# PX4uNode_V0_1_2.net
KiCad netlist of a schematic drawn in EAGLE
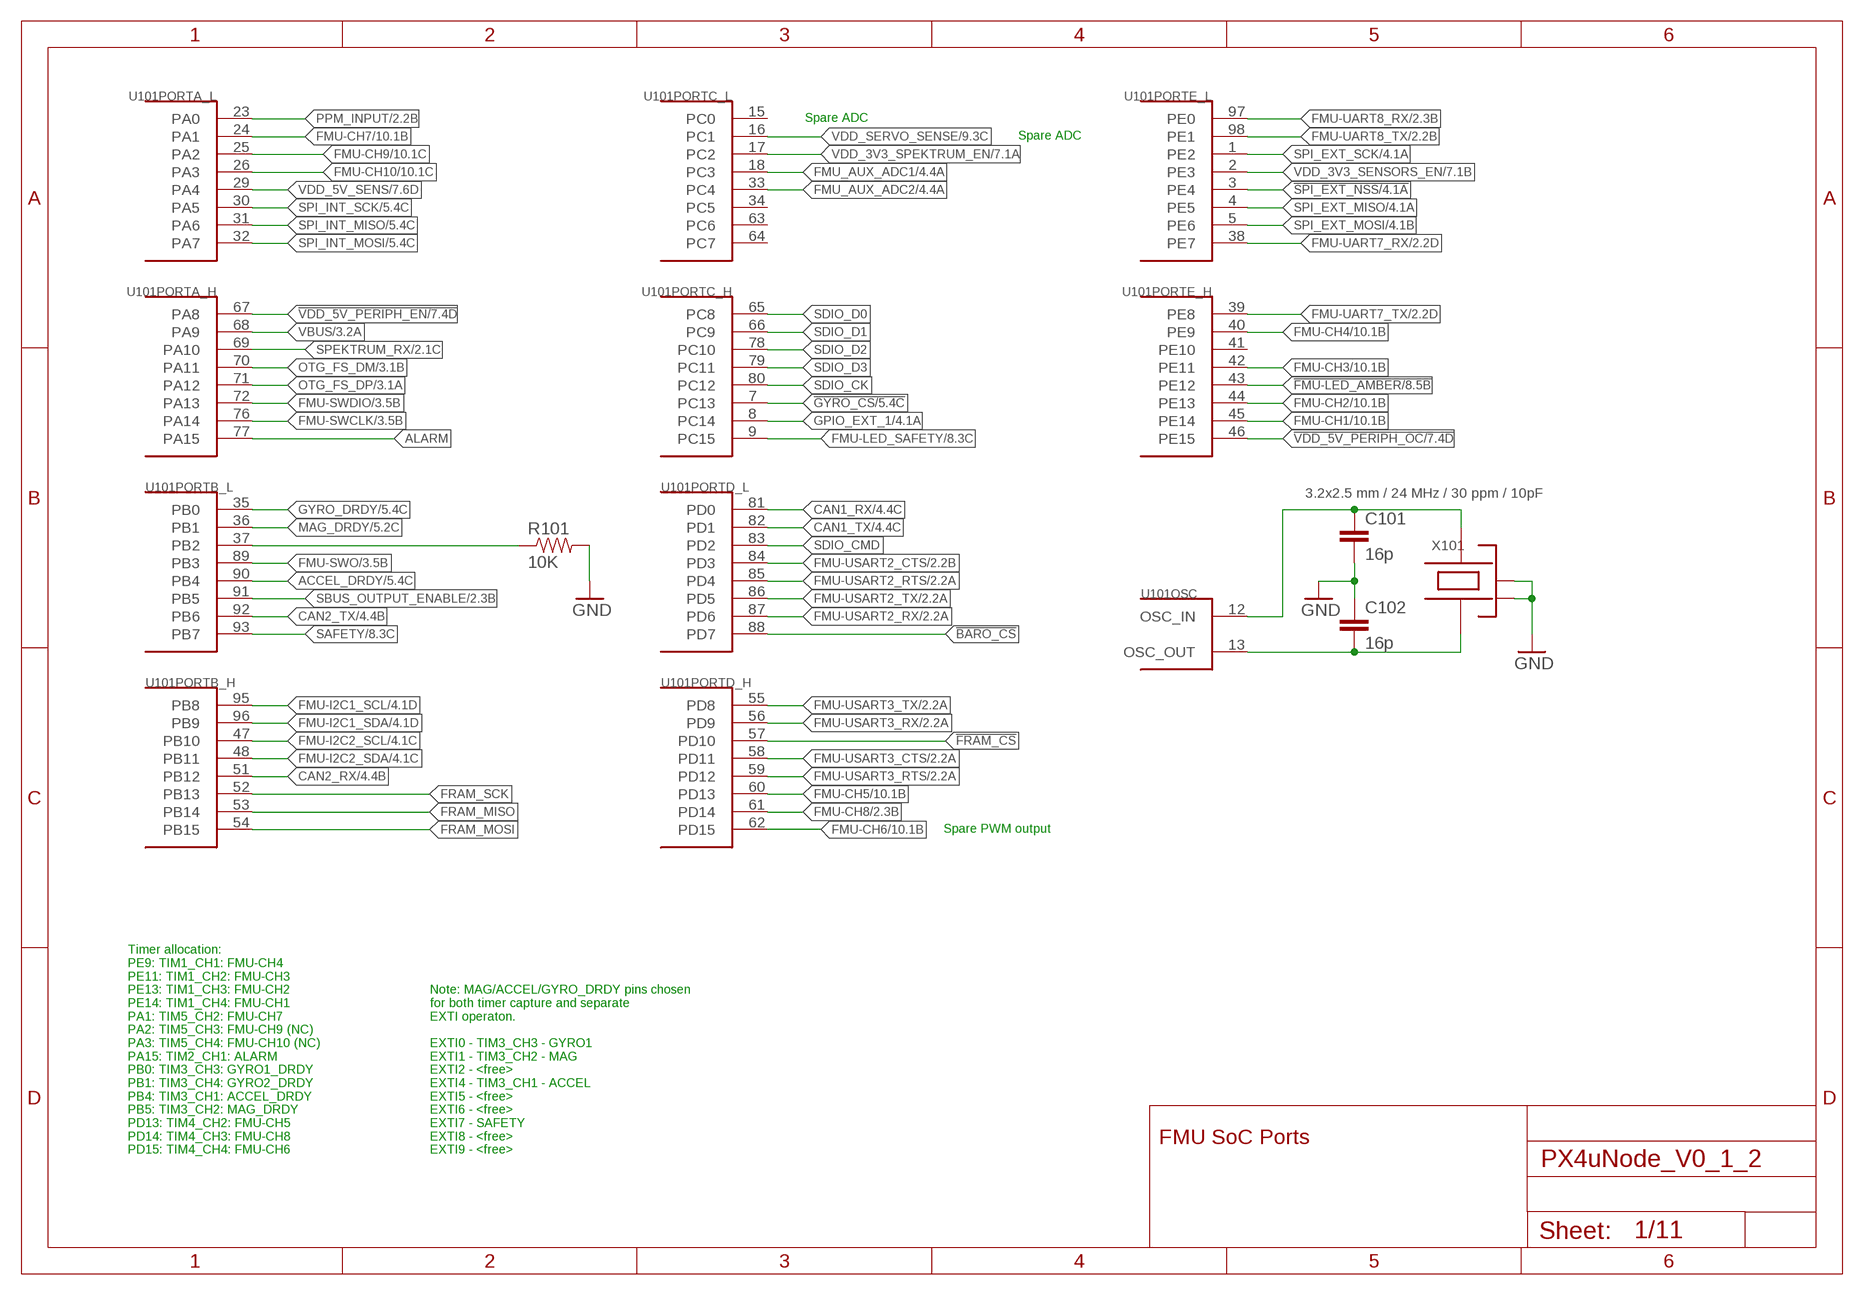
[diagram p0: schematic, sheet 1]
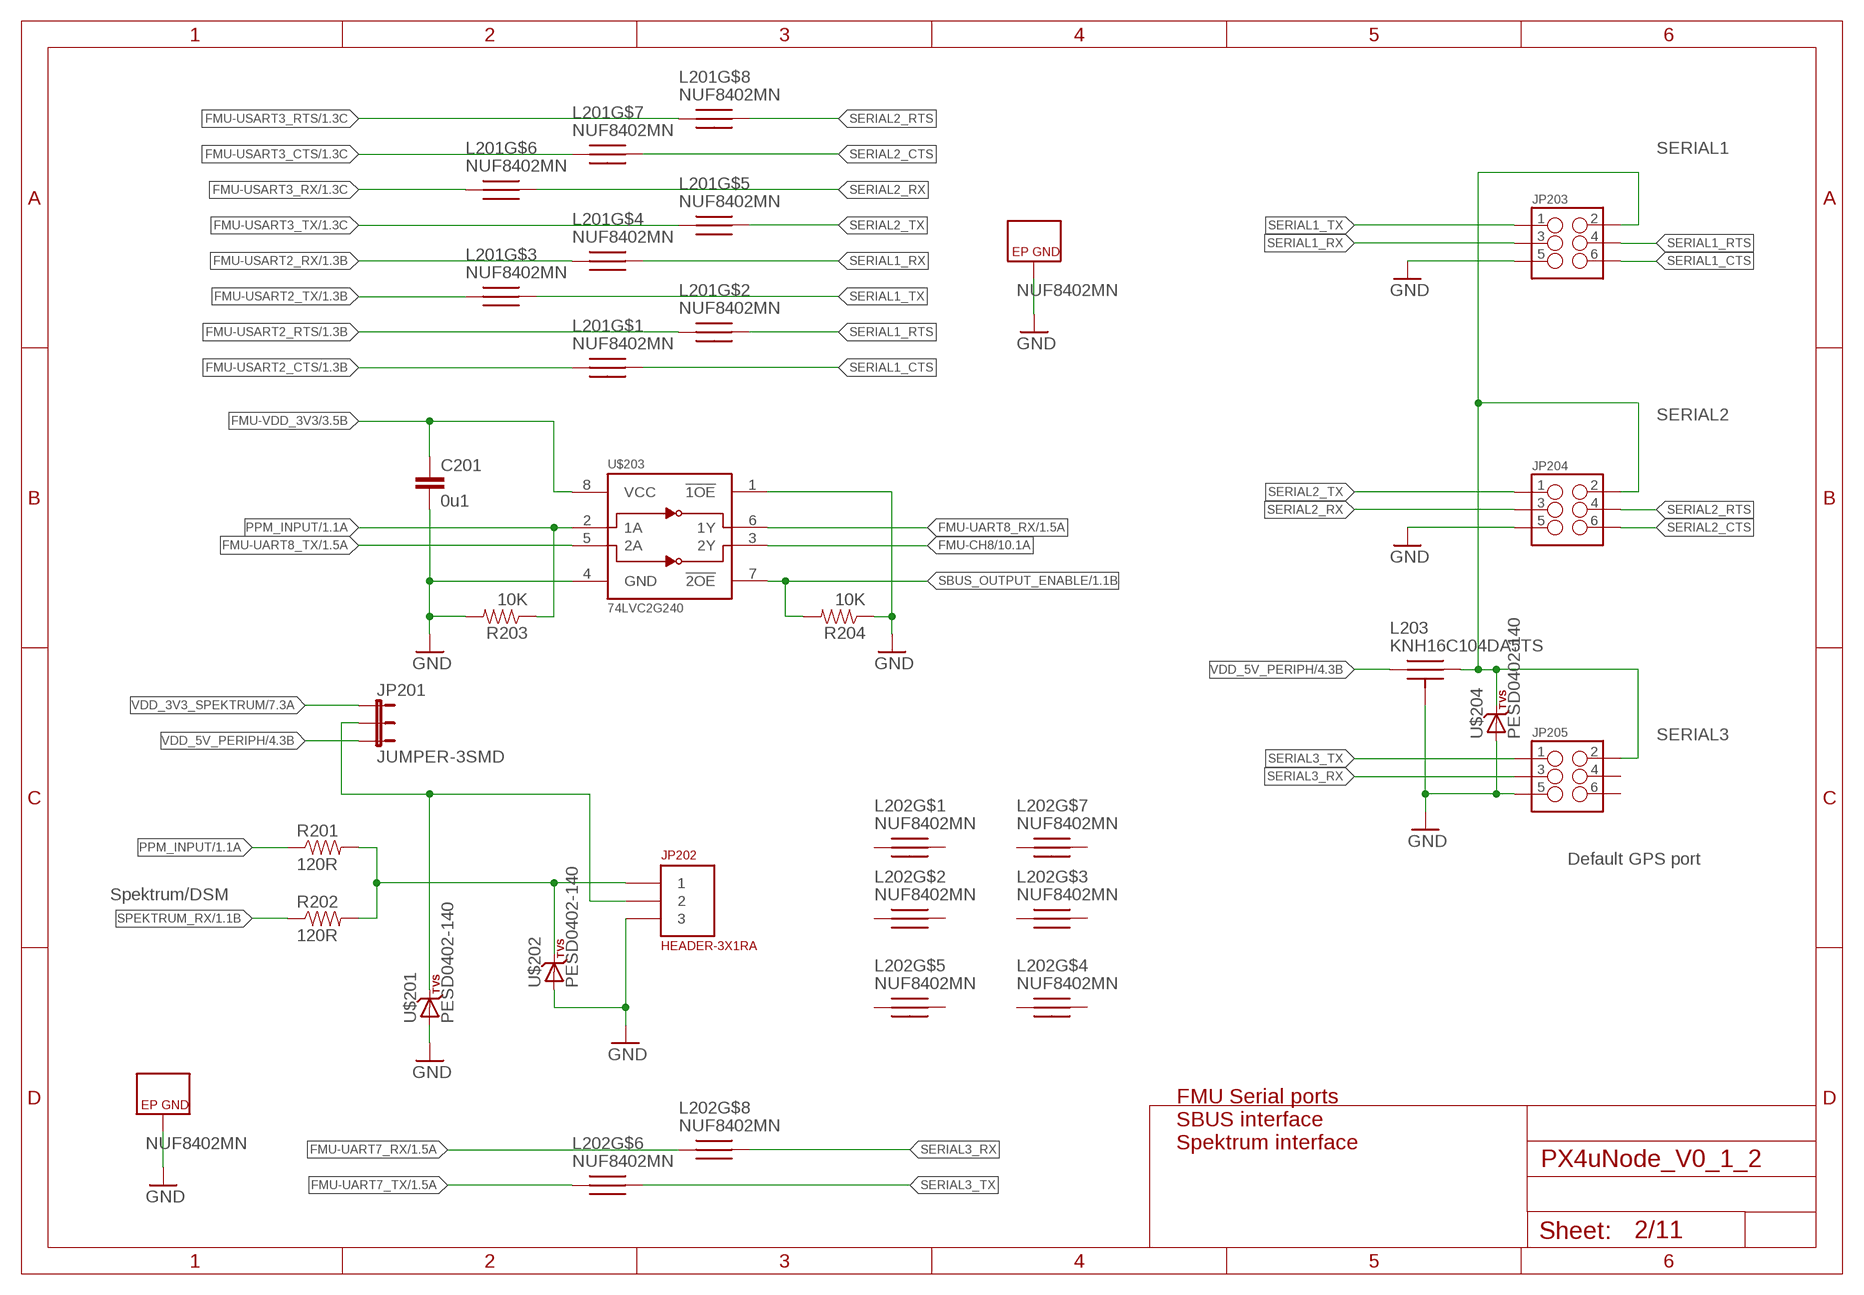
[diagram p1: schematic, sheet 2]
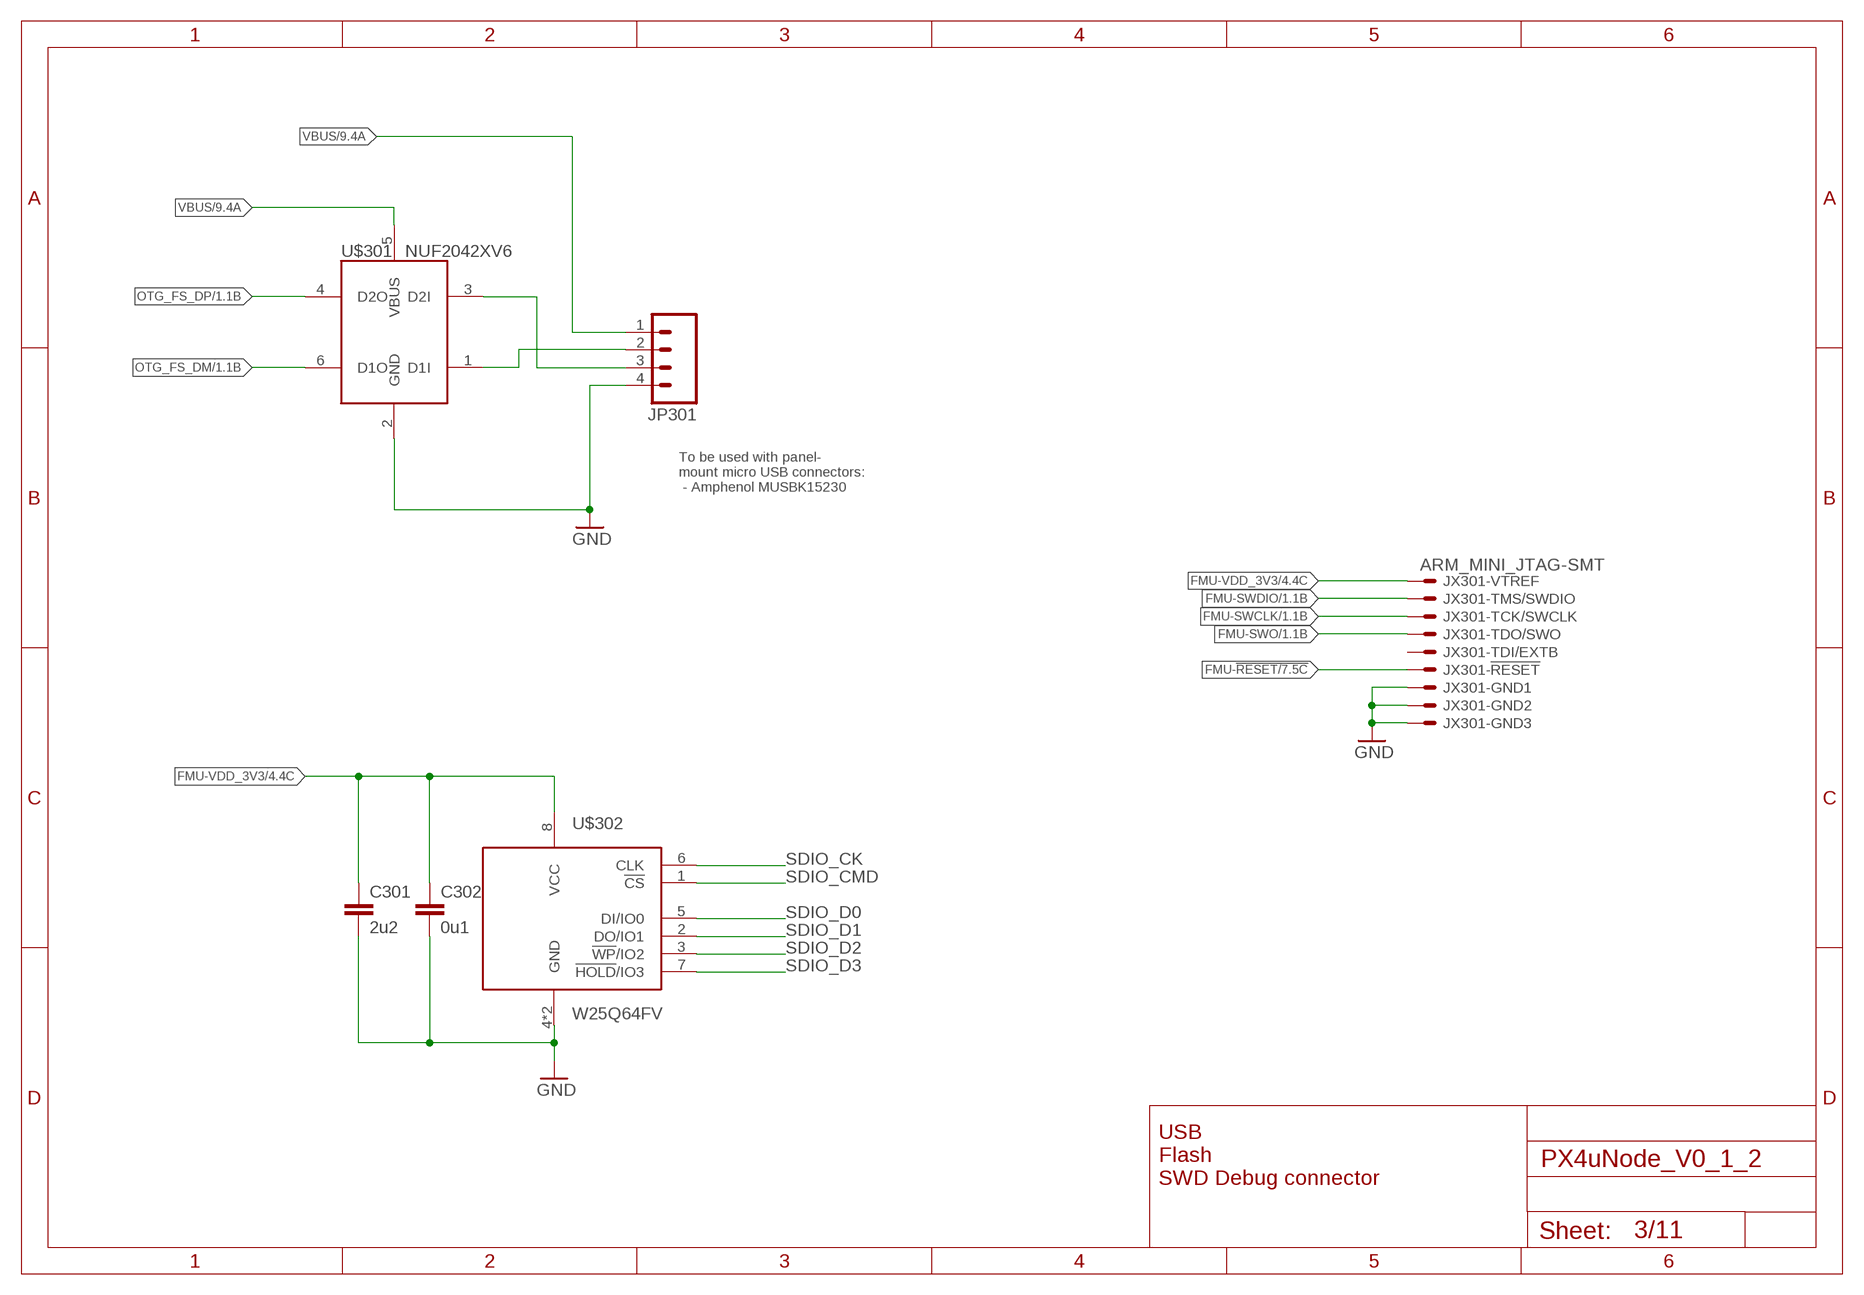
[diagram p2: schematic, sheet 3]
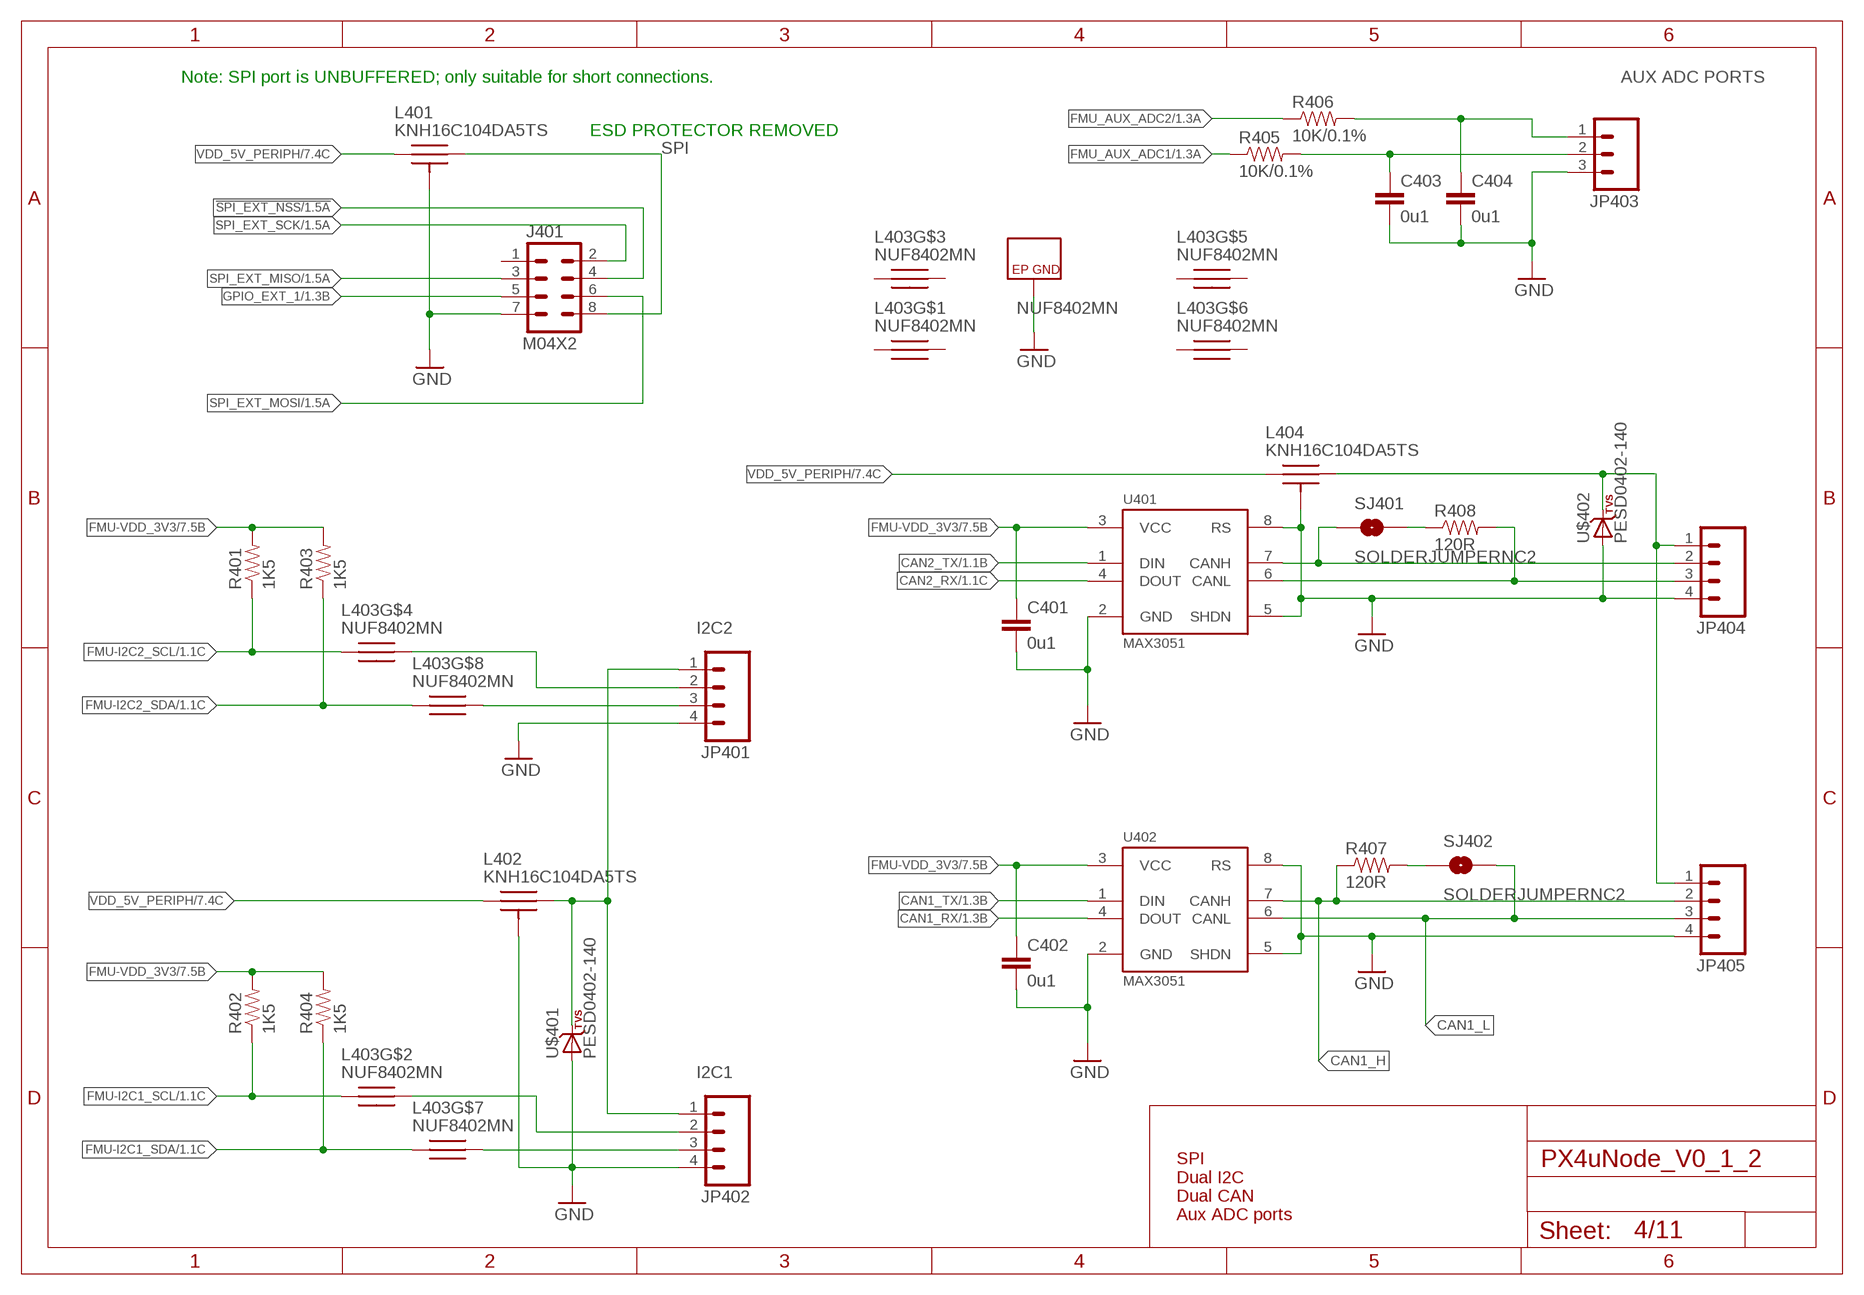
[diagram p3: schematic, sheet 4]
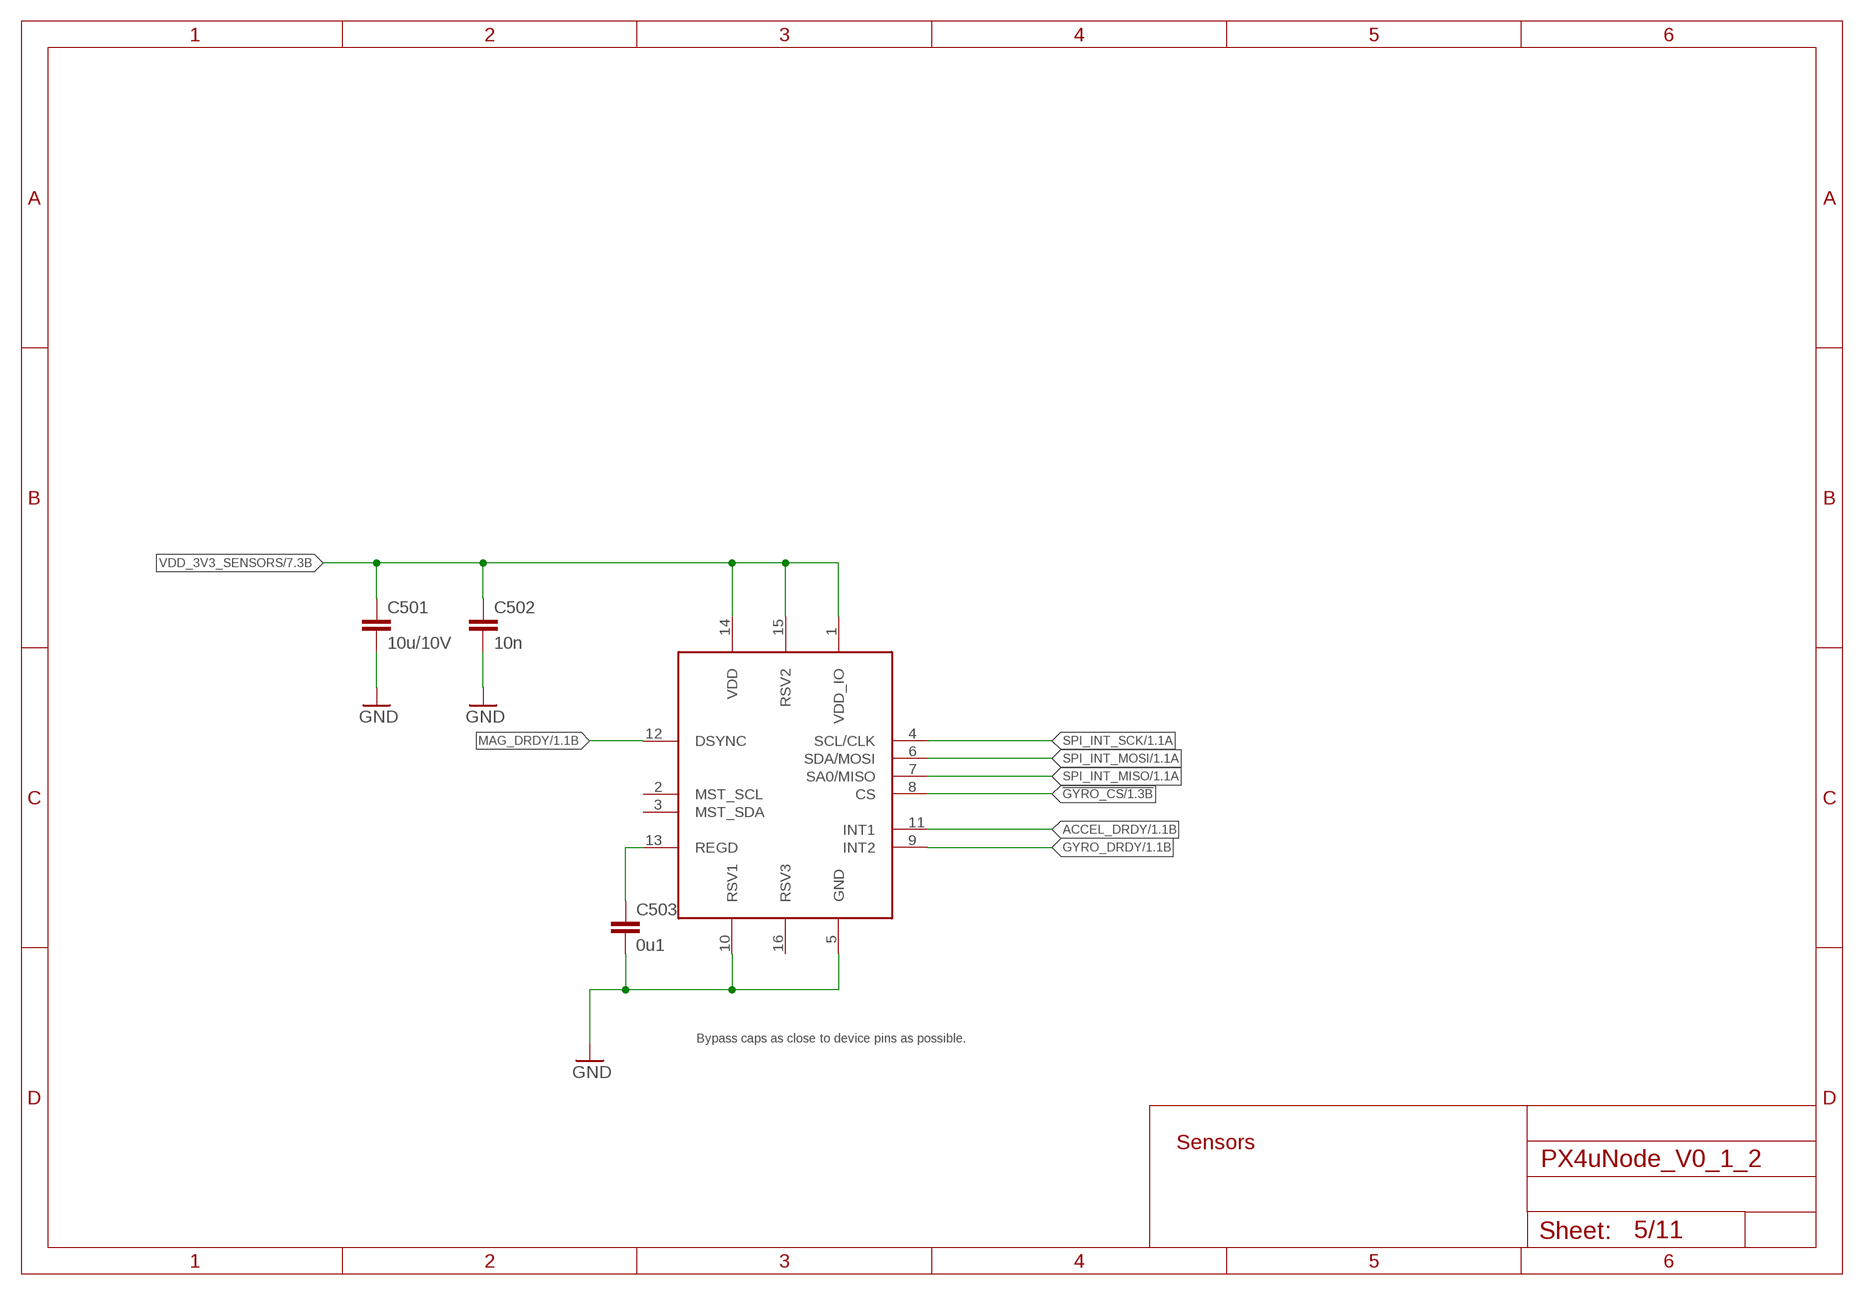
[diagram p4: schematic, sheet 5]
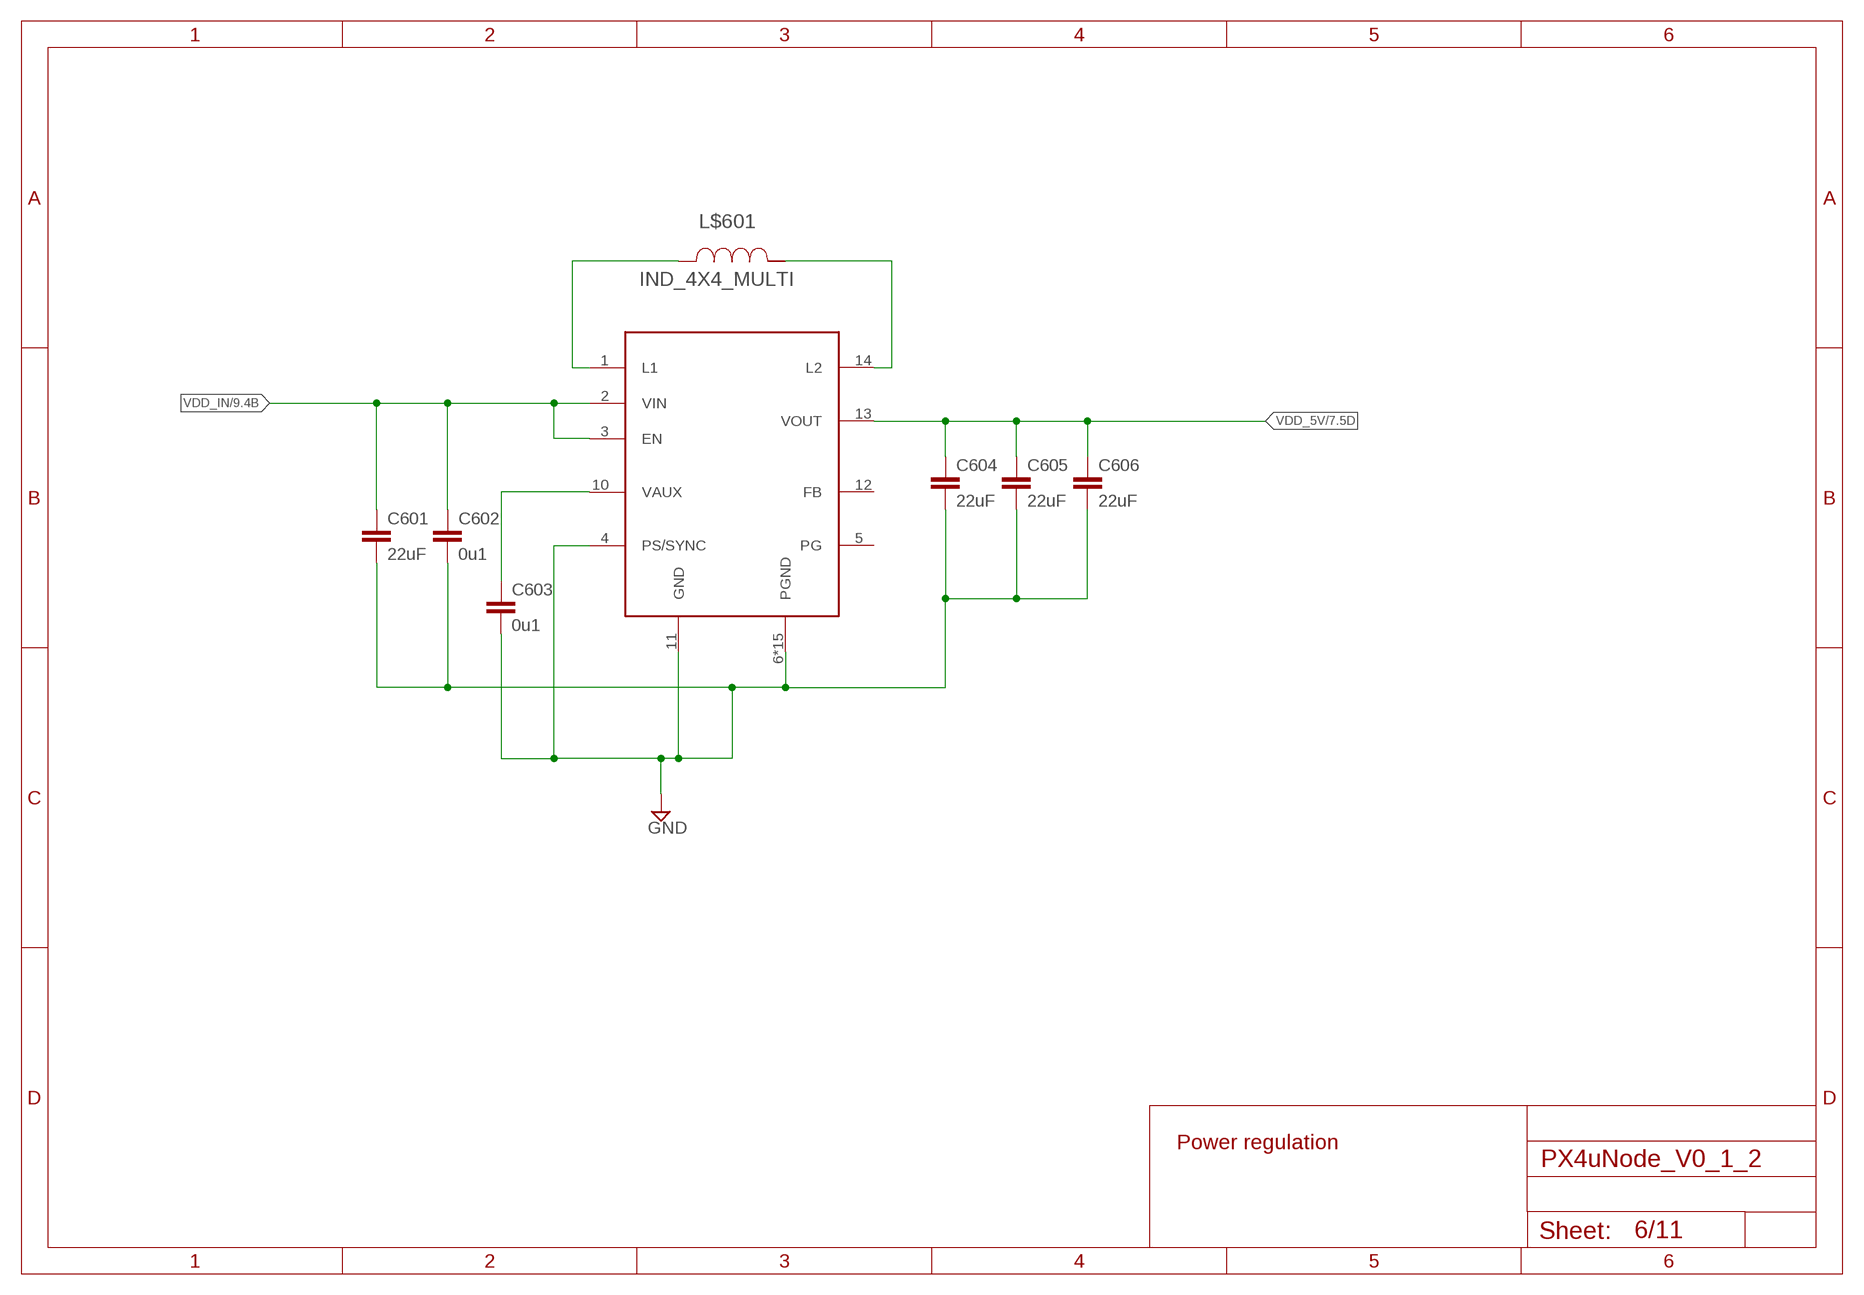
[diagram p5: schematic, sheet 6]
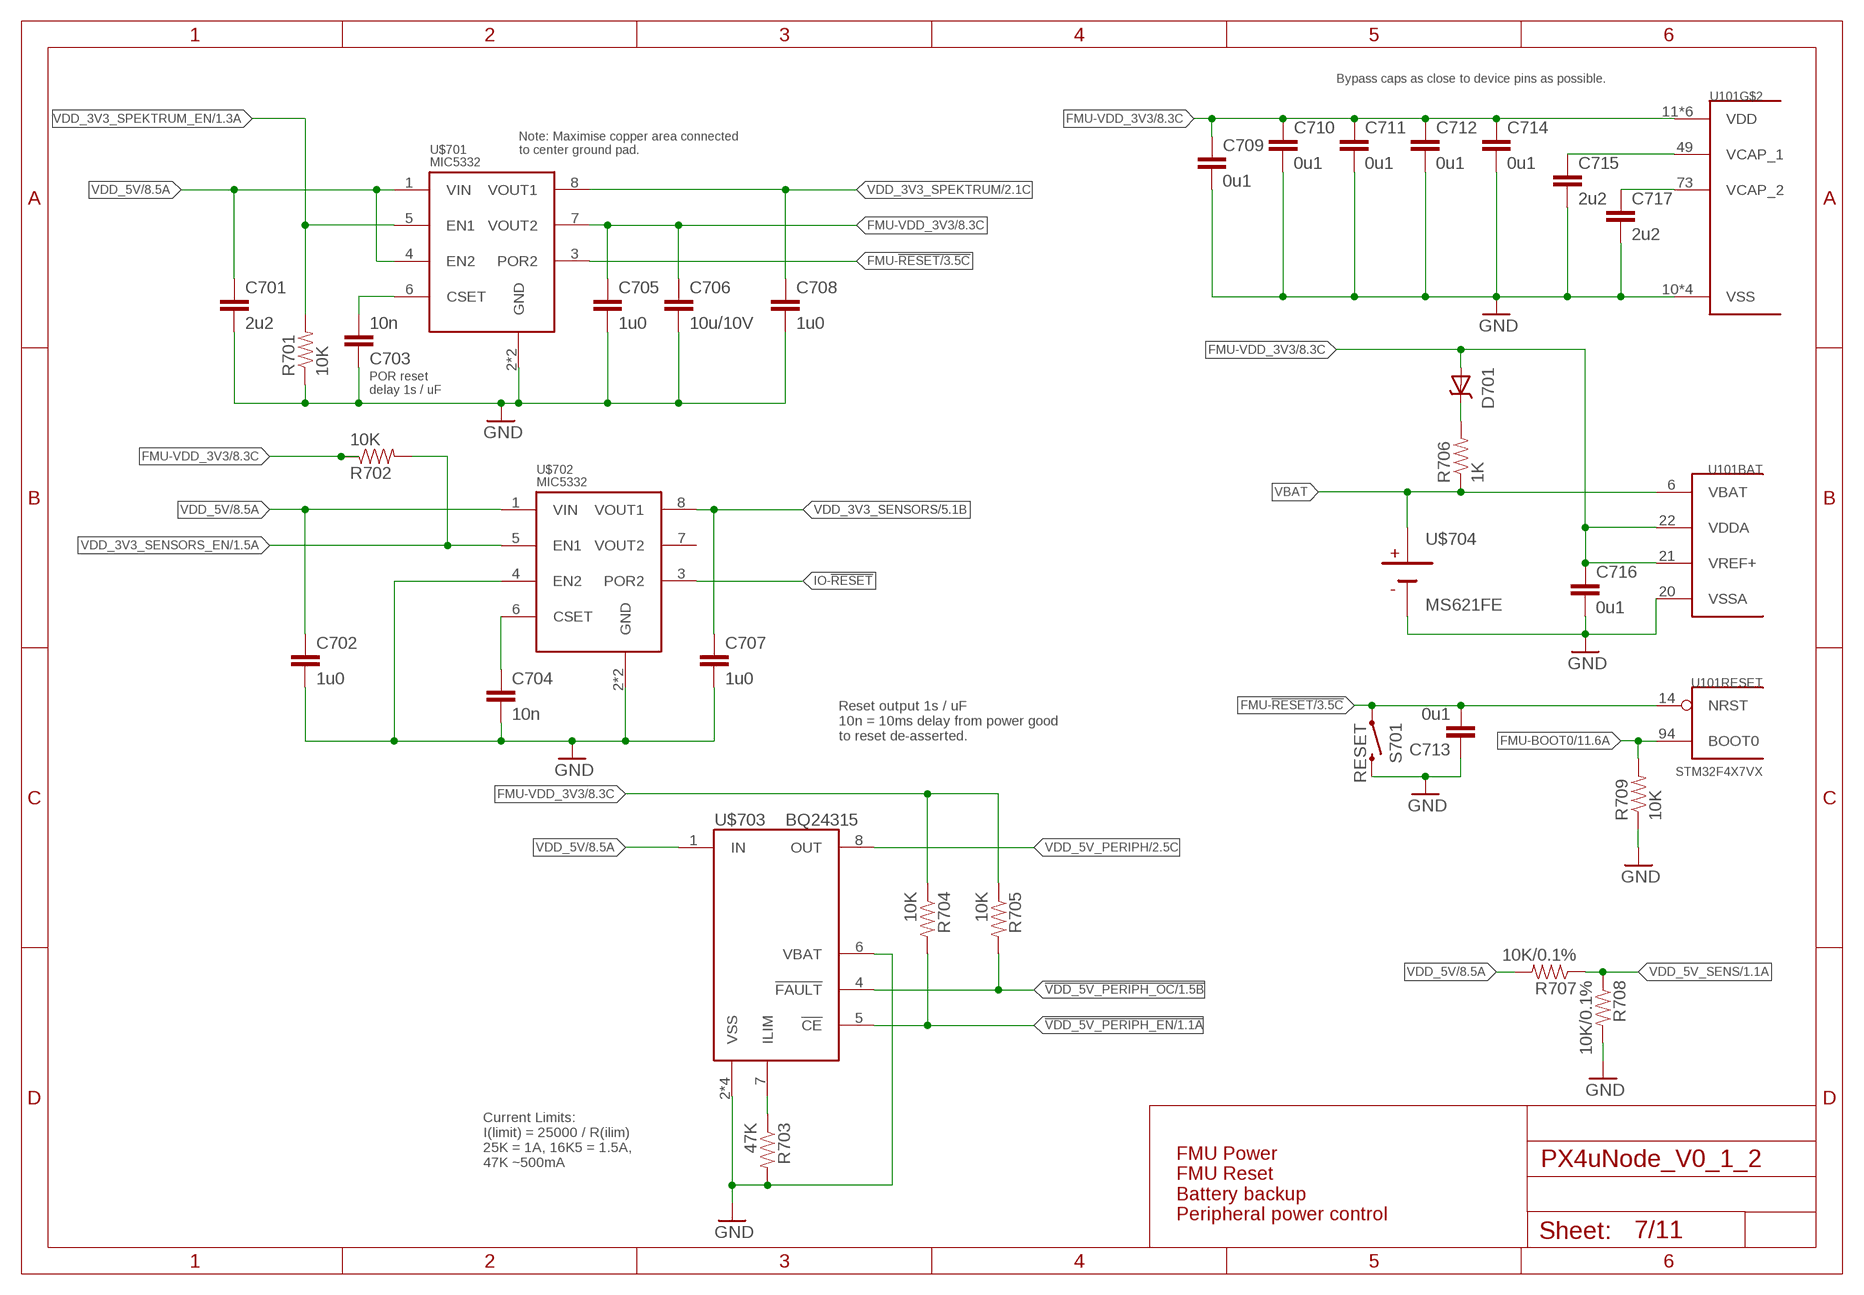
[diagram p6: schematic, sheet 7]
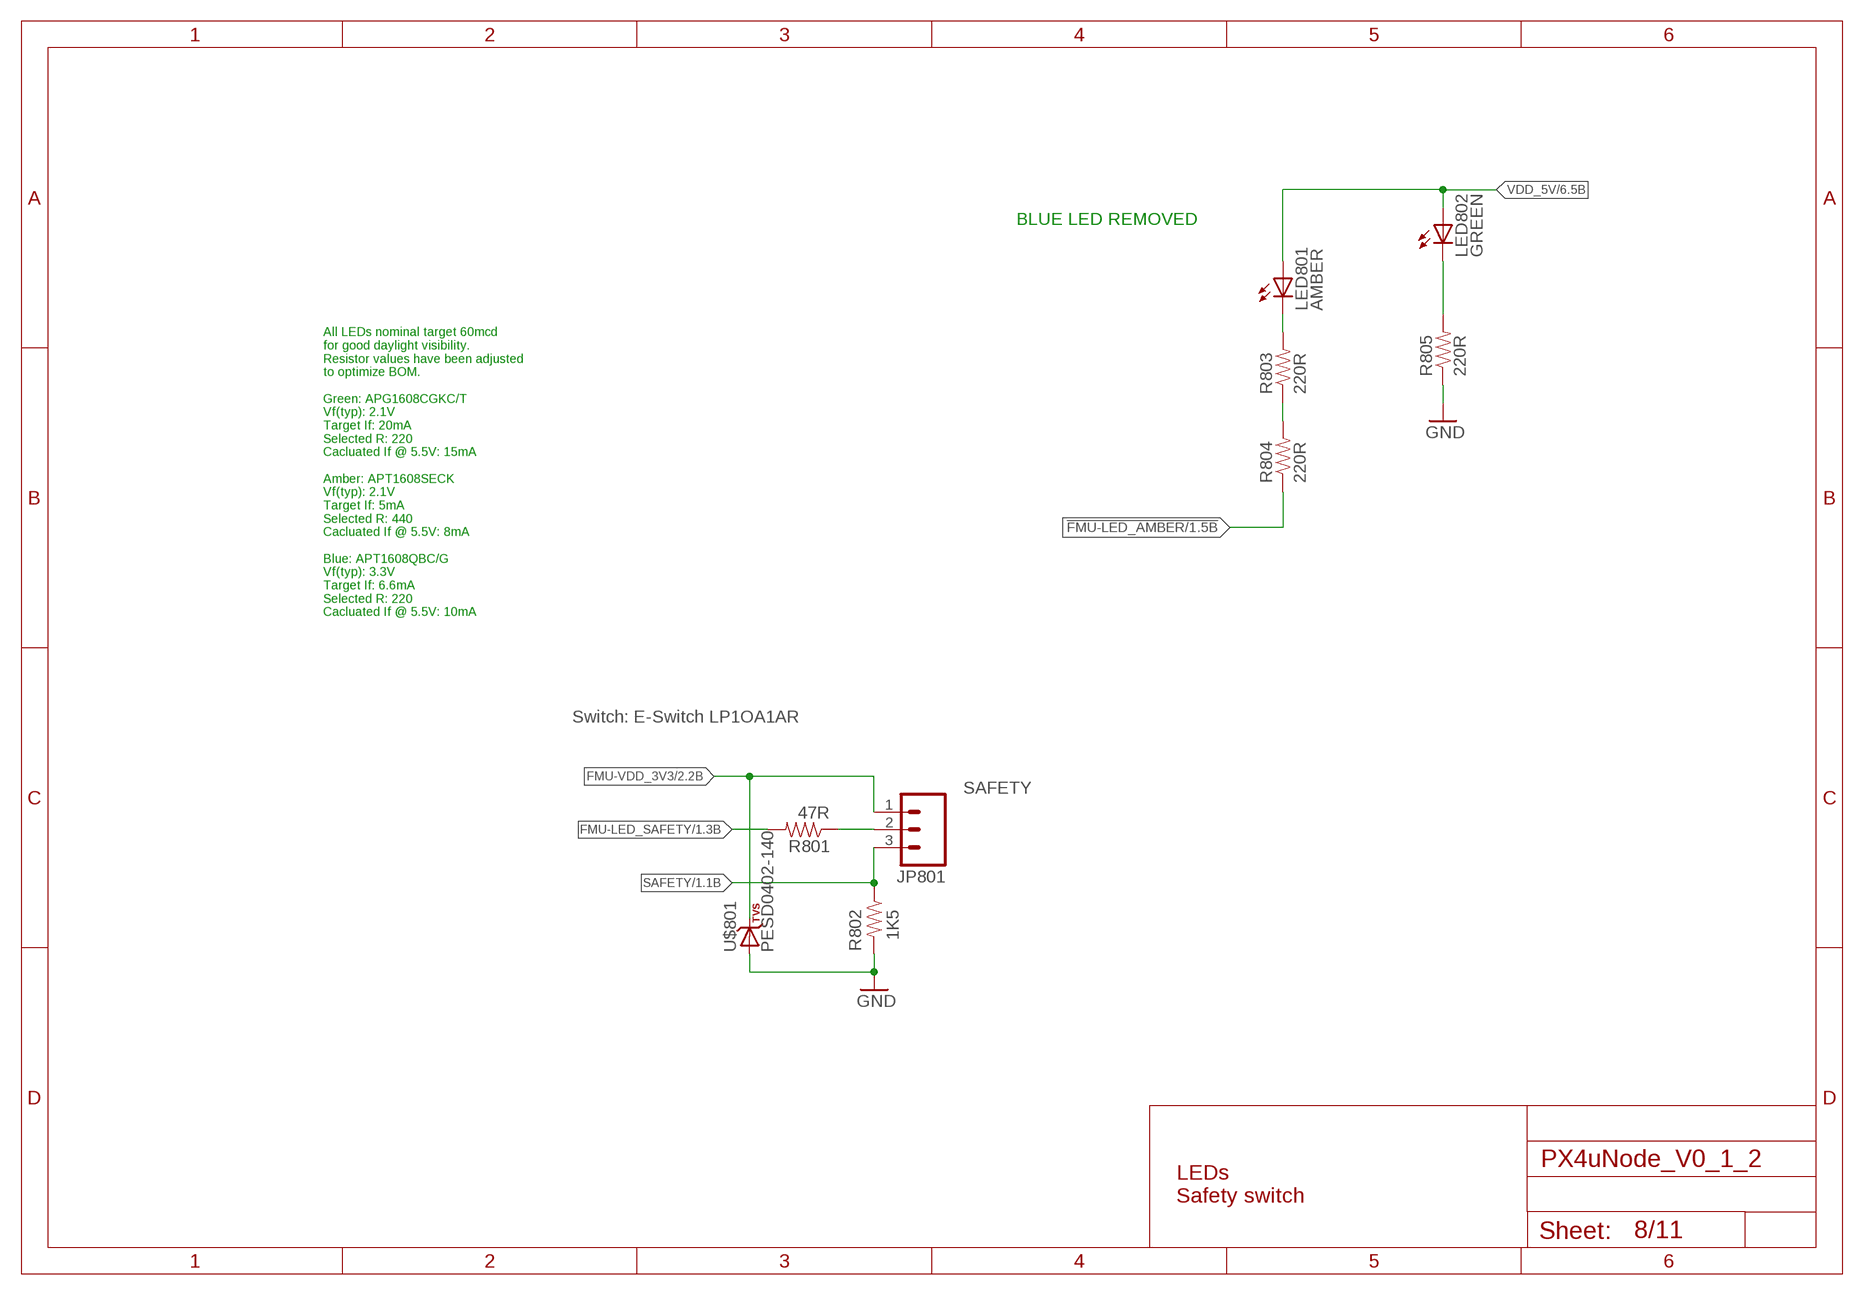
[diagram p7: schematic, sheet 8]
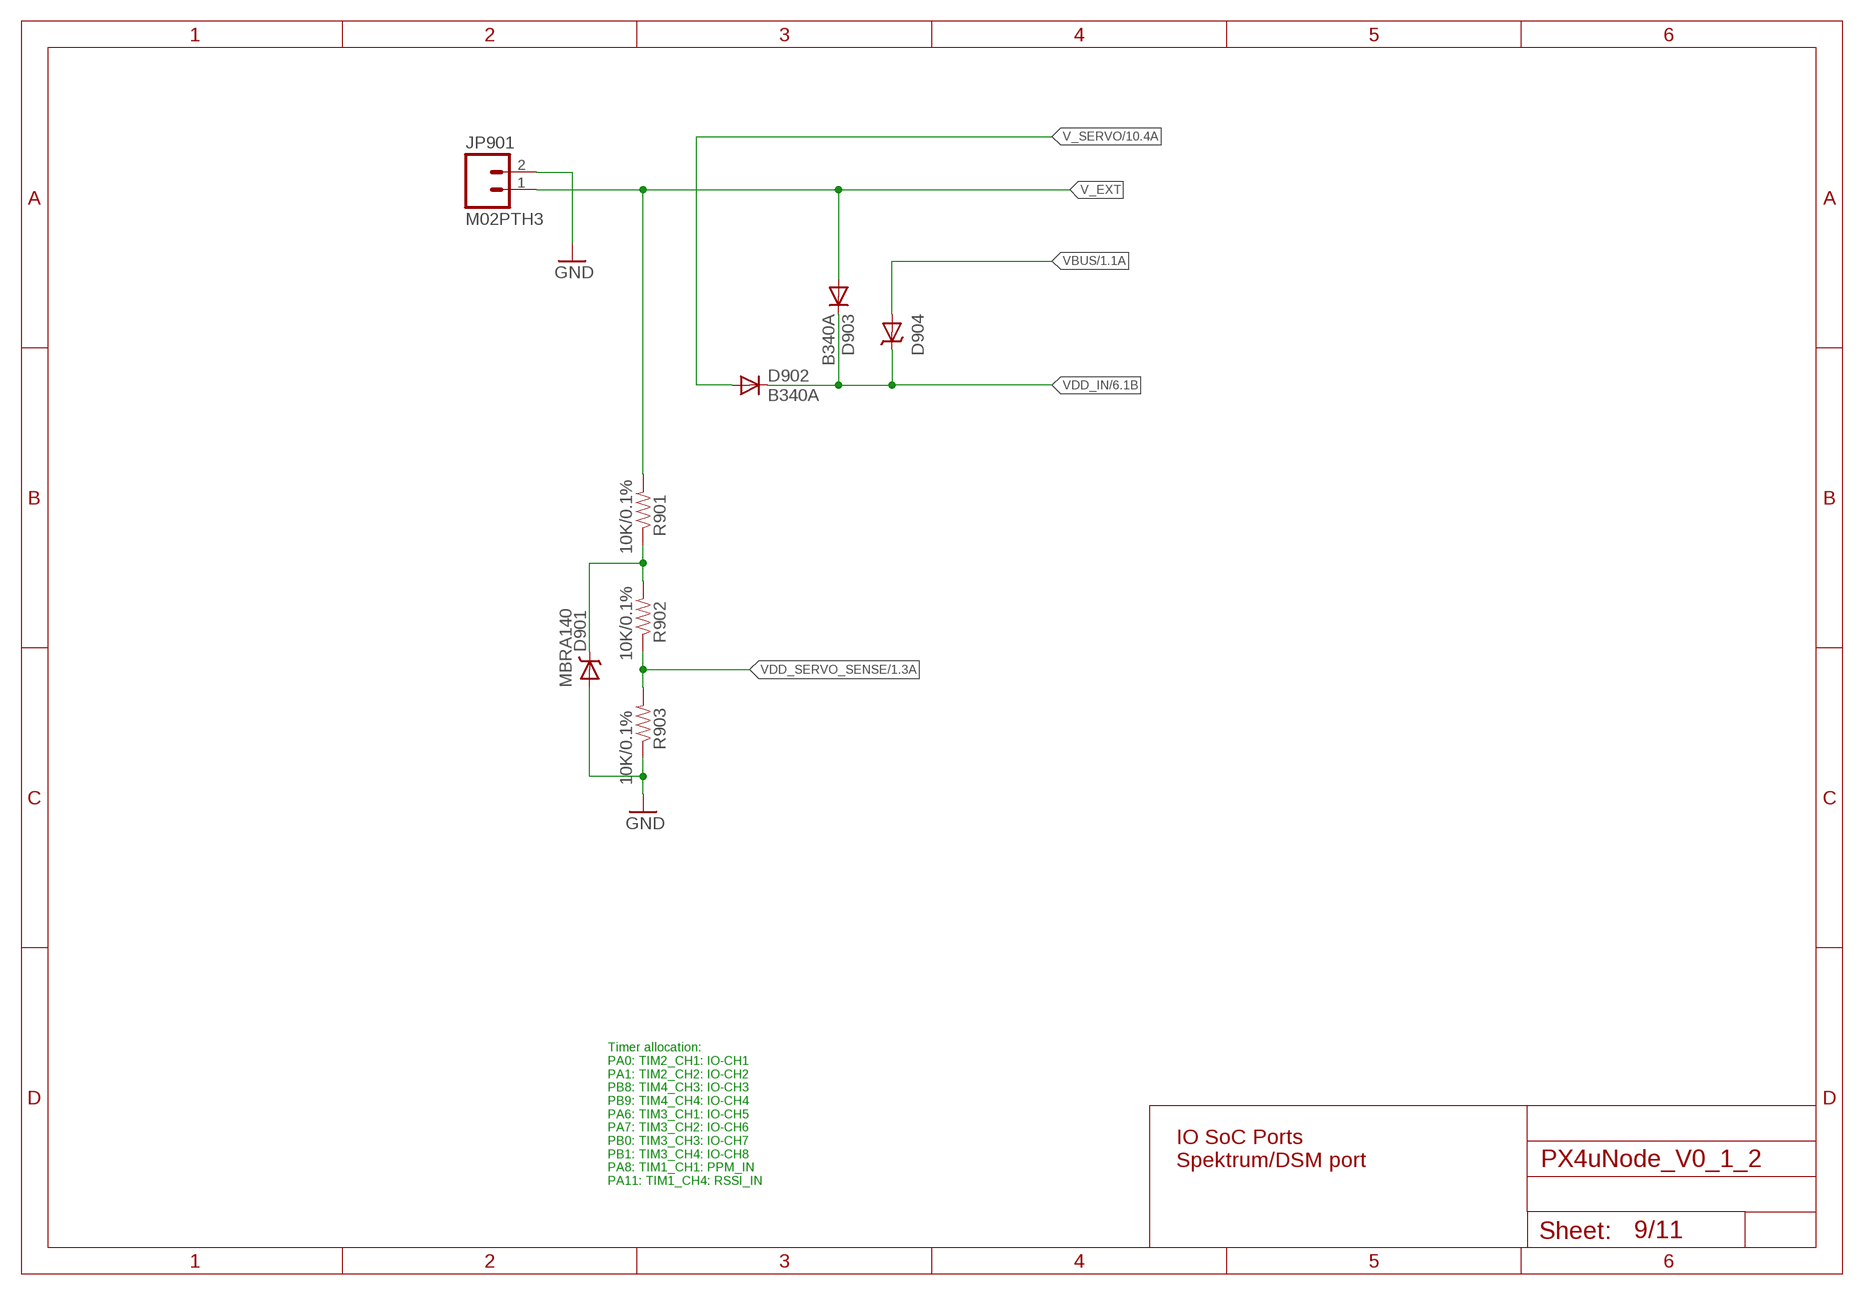
[diagram p8: schematic, sheet 9]
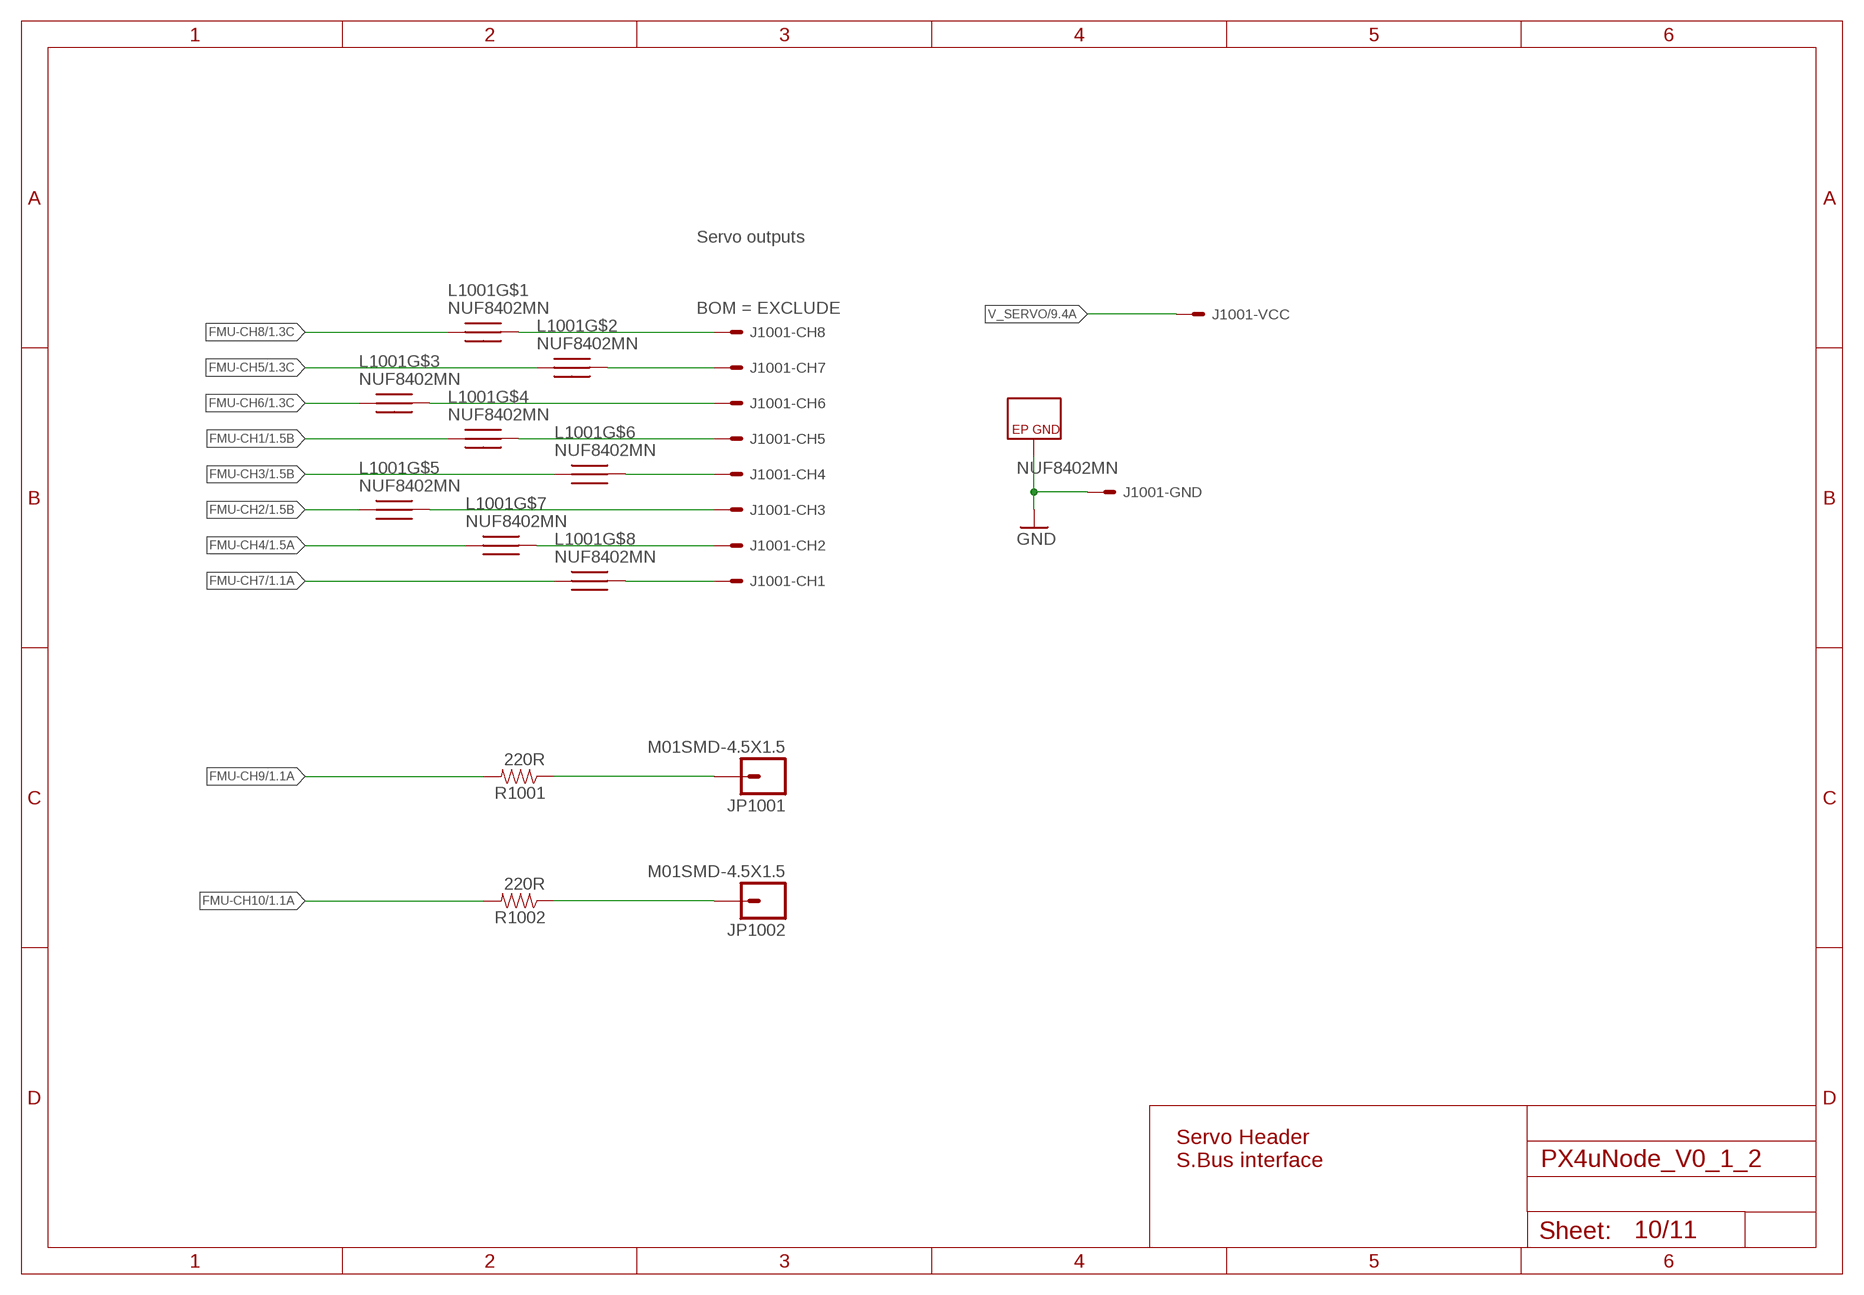
[diagram p9: schematic, sheet 10]
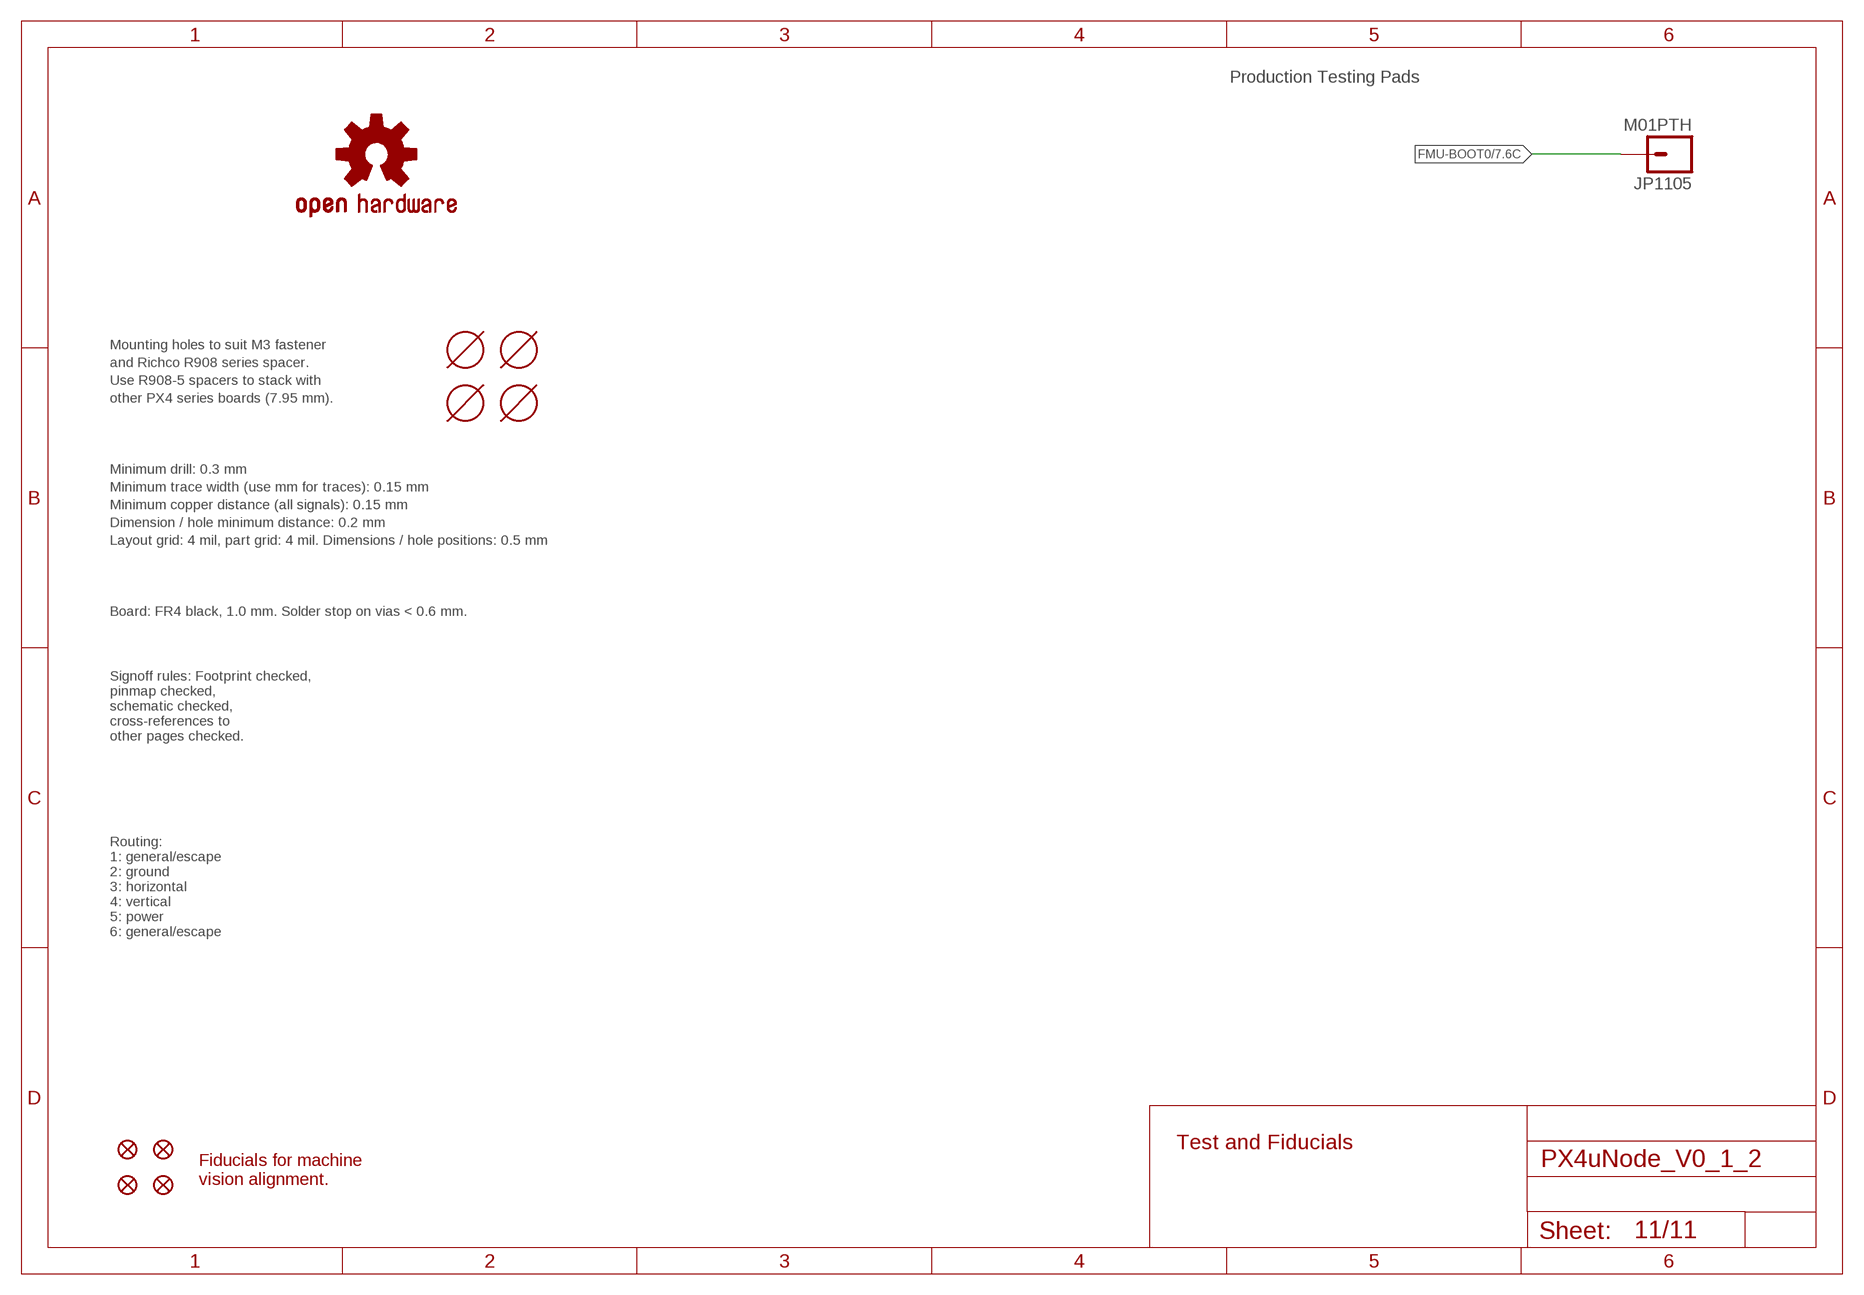
[diagram p10: schematic, sheet 11]

(export (version "E")
  (design (tool "Eeschema 10.0.6"))
  (components
    (comp (ref "C301")
      (value "2u2")
      (footprint "eagle-import:0603-CAP")
      (fields (field (name "PARTNO") "C1608Y5V1C225Z"))
      (libsource (lib "eagle-import") (part "CAP0603"))
    )
    (comp (ref "C302")
      (value "0u1")
      (footprint "eagle-import:0402-CAP")
      (fields (field (name "PARTNO") "CC0402ZRY5V7BB104"))
      (libsource (lib "eagle-import") (part "CAP0402"))
    )
    (comp (ref "JP301")
      (value "M04PTH")
      (footprint "eagle-import:1X04")
      (libsource (lib "eagle-import") (part "M04PTH"))
    )
    (comp (ref "JX301")
      (value "ARM_MINI_JTAG-SMT")
      (footprint "eagle-import:FTSH-105-01-XXX-DV-K")
      (fields (field (name "BOM") "EXCLUDE") (field (name "PARTNO") "M50-3900542"))
      (libsource (lib "eagle-import") (part "ARM_MINI_JTAG-SMT"))
    )
    (comp (ref "U$301")
      (value "NUF2042XV6")
      (footprint "eagle-import:SOT563-6")
      (libsource (lib "eagle-import") (part "NUF2042XV6"))
    )
    (comp (ref "U$302")
      (value "W25Q64FV")
      (footprint "eagle-import:WSON-8-5X6")
      (fields (field (name "PARTNO") "W25Q64FVZP"))
      (libsource (lib "eagle-import") (part "W25Q64FV"))
    )
    (comp (ref "D901")
      (value "DIODE-SCHOTTKY")
      (footprint "eagle-import:SOD-523")
      (fields (field (name "PARTNO") "MBRA140"))
      (libsource (lib "eagle-import") (part "DIODE-SCHOTTKY"))
    )
    (comp (ref "D902")
      (value "B340A")
      (footprint "eagle-import:SMA-DIODE")
      (libsource (lib "eagle-import") (part "DIODESMA"))
    )
    (comp (ref "D903")
      (value "B340A")
      (footprint "eagle-import:SMA-DIODE")
      (libsource (lib "eagle-import") (part "DIODESMA"))
    )
    (comp (ref "D904")
      (value "MSS1P4-M3")
      (footprint "eagle-import:MICROSMP")
      (fields (field (name "PARTNO") "MSS1P4-M3/89A"))
      (libsource (lib "eagle-import") (part "DIODE-SCHOTTKY_MSMP"))
    )
    (comp (ref "JP901")
      (value "M02PTH3")
      (footprint "eagle-import:1X02_LONGPADS")
      (libsource (lib "eagle-import") (part "M02PTH3"))
    )
    (comp (ref "R901")
      (value "10K/0.1%")
      (footprint "eagle-import:0402-RES")
      (fields (field (name "PARTNO") "ERA-2AEB103X"))
      (libsource (lib "eagle-import") (part "RESISTOR0402-RES"))
    )
    (comp (ref "R902")
      (value "10K/0.1%")
      (footprint "eagle-import:0402-RES")
      (fields (field (name "PARTNO") "ERA-2AEB103X"))
      (libsource (lib "eagle-import") (part "RESISTOR0402-RES"))
    )
    (comp (ref "R903")
      (value "10K/0.1%")
      (footprint "eagle-import:0402-RES")
      (fields (field (name "PARTNO") "ERA-2AEB103X"))
      (libsource (lib "eagle-import") (part "RESISTOR0402-RES"))
    )
    (comp (ref "C601")
      (value "22uF")
      (footprint "eagle-import:1210")
      (fields (field (name "PARTNO") "C3225X7R1C226M250AC"))
      (libsource (lib "eagle-import") (part "22UF-16V-20%-(1210)"))
    )
    (comp (ref "C602")
      (value "0u1")
      (footprint "eagle-import:0402-CAP")
      (fields (field (name "PARTNO") "CC0402ZRY5V7BB104"))
      (libsource (lib "eagle-import") (part "CAP0402"))
    )
    (comp (ref "C603")
      (value "0u1")
      (footprint "eagle-import:0402-CAP")
      (fields (field (name "PARTNO") "CC0402ZRY5V7BB104"))
      (libsource (lib "eagle-import") (part "CAP0402"))
    )
    (comp (ref "C604")
      (value "22uF")
      (footprint "eagle-import:1210")
      (fields (field (name "PARTNO") "C3225X7R1C226M250AC"))
      (libsource (lib "eagle-import") (part "22UF-16V-20%-(1210)"))
    )
    (comp (ref "C605")
      (value "22uF")
      (footprint "eagle-import:1210")
      (fields (field (name "PARTNO") "C3225X7R1C226M250AC"))
      (libsource (lib "eagle-import") (part "22UF-16V-20%-(1210)"))
    )
    (comp (ref "C606")
      (value "22uF")
      (footprint "eagle-import:1210")
      (fields (field (name "PARTNO") "C3225X7R1C226M250AC"))
      (libsource (lib "eagle-import") (part "22UF-16V-20%-(1210)"))
    )
    (comp (ref "L$601")
      (value "IND_4X4_MULTI")
      (footprint "eagle-import:IND_4X4_MULTI")
      (fields (field (name "MANUFACTURER_PART_NUMBER") "XFL4020-222MEB"))
      (libsource (lib "eagle-import") (part "IND_4X4_MULTI"))
    )
    (comp (ref "U$601")
      (value "TPS6303X")
      (footprint "eagle-import:PWSON10")
      (fields (field (name "PARTNO") "TPS63061DSCT"))
      (libsource (lib "eagle-import") (part "TPS6303X"))
    )
    (comp (ref "C201")
      (value "0u1")
      (footprint "eagle-import:0402-CAP")
      (fields (field (name "PARTNO") "CC0402ZRY5V7BB104"))
      (libsource (lib "eagle-import") (part "CAP0402"))
    )
    (comp (ref "JP201")
      (value "JUMPER-3SMD")
      (footprint "eagle-import:SJ_3")
      (libsource (lib "eagle-import") (part "JUMPER-3SMD"))
    )
    (comp (ref "JP202")
      (value "HEADER-3X1RA")
      (footprint "eagle-import:3X1RA")
      (libsource (lib "eagle-import") (part "HEADER-3X1RA"))
    )
    (comp (ref "JP203")
      (value "M03X22X3_SILK_SM")
      (footprint "eagle-import:2X3")
      (libsource (lib "eagle-import") (part "M03X22X3_SILK_SM"))
    )
    (comp (ref "JP204")
      (value "M03X22X3_SILK_SM")
      (footprint "eagle-import:2X3")
      (libsource (lib "eagle-import") (part "M03X22X3_SILK_SM"))
    )
    (comp (ref "JP205")
      (value "M03X22X3_SILK_SM")
      (footprint "eagle-import:2X3")
      (libsource (lib "eagle-import") (part "M03X22X3_SILK_SM"))
    )
    (comp (ref "L201")
      (value "NUF8402MN")
      (footprint "eagle-import:DFN16-THIN")
      (fields (field (name "PARTNO") "NUF8402MN"))
      (libsource (lib "eagle-import") (part "NUF8402MN"))
    )
    (comp (ref "L202")
      (value "NUF8402MN")
      (footprint "eagle-import:DFN16-THIN")
      (fields (field (name "PARTNO") "NUF8402MN"))
      (libsource (lib "eagle-import") (part "NUF8402MN"))
    )
    (comp (ref "L203")
      (value "KNH16C104DA5TS")
      (footprint "eagle-import:KYOCERA-KNH16-DA")
      (libsource (lib "eagle-import") (part "KNH16C104DA5TS"))
    )
    (comp (ref "R201")
      (value "120R")
      (footprint "eagle-import:0402-RES")
      (fields (field (name "PARTNO") "RC0402FR-07120RL"))
      (libsource (lib "eagle-import") (part "RESISTOR0402-RES"))
    )
    (comp (ref "R202")
      (value "120R")
      (footprint "eagle-import:0402-RES")
      (fields (field (name "PARTNO") "RC0402FR-07120RL"))
      (libsource (lib "eagle-import") (part "RESISTOR0402-RES"))
    )
    (comp (ref "R203")
      (value "10K")
      (footprint "eagle-import:0402-RES")
      (fields (field (name "PARTNO") "RC0402FR-0710KL"))
      (libsource (lib "eagle-import") (part "RESISTOR0402-RES"))
    )
    (comp (ref "R204")
      (value "10K")
      (footprint "eagle-import:0402-RES")
      (fields (field (name "PARTNO") "RC0402FR-0710KL"))
      (libsource (lib "eagle-import") (part "RESISTOR0402-RES"))
    )
    (comp (ref "U$201")
      (value "PESD0402-140")
      (footprint "eagle-import:0402-TVS")
      (libsource (lib "eagle-import") (part "DIODE-TVS"))
    )
    (comp (ref "U$202")
      (value "PESD0402-140")
      (footprint "eagle-import:0402-TVS")
      (libsource (lib "eagle-import") (part "DIODE-TVS"))
    )
    (comp (ref "U$203")
      (value "74LVC2G240")
      (footprint "eagle-import:VSSOP8")
      (libsource (lib "eagle-import") (part "74LVC2G240"))
    )
    (comp (ref "U$204")
      (value "PESD0402-140")
      (footprint "eagle-import:0402-TVS")
      (libsource (lib "eagle-import") (part "DIODE-TVS"))
    )
    (comp (ref "C701")
      (value "2u2")
      (footprint "eagle-import:0603-CAP")
      (fields (field (name "PARTNO") "C1608Y5V1C225Z"))
      (libsource (lib "eagle-import") (part "CAP0603"))
    )
    (comp (ref "C702")
      (value "1u0")
      (footprint "eagle-import:0603-CAP")
      (fields (field (name "PARTNO") "CC0603ZRY5V7BB105"))
      (libsource (lib "eagle-import") (part "CAP0603"))
    )
    (comp (ref "C703")
      (value "10n")
      (footprint "eagle-import:0402-CAP")
      (fields (field (name "PARTNO") "CC0402KRX7R7BB103"))
      (libsource (lib "eagle-import") (part "CAP0402"))
    )
    (comp (ref "C704")
      (value "10n")
      (footprint "eagle-import:0402-CAP")
      (fields (field (name "PARTNO") "CC0402KRX7R7BB103"))
      (libsource (lib "eagle-import") (part "CAP0402"))
    )
    (comp (ref "C705")
      (value "1u0")
      (footprint "eagle-import:0603-CAP")
      (fields (field (name "PARTNO") "CC0603ZRY5V7BB105"))
      (libsource (lib "eagle-import") (part "CAP0603"))
    )
    (comp (ref "C706")
      (value "10u/10V")
      (footprint "eagle-import:0805-CAP")
      (fields (field (name "PARTNO") "CC0805ZKY5V6BB106"))
      (libsource (lib "eagle-import") (part "CAP0805"))
    )
    (comp (ref "C707")
      (value "1u0")
      (footprint "eagle-import:0603-CAP")
      (fields (field (name "PARTNO") "CC0603ZRY5V7BB105"))
      (libsource (lib "eagle-import") (part "CAP0603"))
    )
    (comp (ref "C708")
      (value "1u0")
      (footprint "eagle-import:0603-CAP")
      (fields (field (name "PARTNO") "CC0603ZRY5V7BB105"))
      (libsource (lib "eagle-import") (part "CAP0603"))
    )
    (comp (ref "C709")
      (value "0u1")
      (footprint "eagle-import:0402-CAP")
      (fields (field (name "PARTNO") "CC0402ZRY5V7BB104"))
      (libsource (lib "eagle-import") (part "CAP0402"))
    )
    (comp (ref "C710")
      (value "0u1")
      (footprint "eagle-import:0402-CAP")
      (fields (field (name "PARTNO") "CC0402ZRY5V7BB104"))
      (libsource (lib "eagle-import") (part "CAP0402"))
    )
    (comp (ref "C711")
      (value "0u1")
      (footprint "eagle-import:0402-CAP")
      (fields (field (name "PARTNO") "CC0402ZRY5V7BB104"))
      (libsource (lib "eagle-import") (part "CAP0402"))
    )
    (comp (ref "C712")
      (value "0u1")
      (footprint "eagle-import:0402-CAP")
      (fields (field (name "PARTNO") "CC0402ZRY5V7BB104"))
      (libsource (lib "eagle-import") (part "CAP0402"))
    )
    (comp (ref "C713")
      (value "0u1")
      (footprint "eagle-import:0402-CAP")
      (fields (field (name "PARTNO") "CC0402ZRY5V7BB104"))
      (libsource (lib "eagle-import") (part "CAP0402"))
    )
    (comp (ref "C714")
      (value "0u1")
      (footprint "eagle-import:0402-CAP")
      (fields (field (name "PARTNO") "CC0402ZRY5V7BB104"))
      (libsource (lib "eagle-import") (part "CAP0402"))
    )
    (comp (ref "C715")
      (value "2u2")
      (footprint "eagle-import:0603-CAP")
      (fields (field (name "PARTNO") "C1608Y5V1C225Z"))
      (libsource (lib "eagle-import") (part "CAP0603"))
    )
    (comp (ref "C716")
      (value "0u1")
      (footprint "eagle-import:0402-CAP")
      (fields (field (name "PARTNO") "CC0402ZRY5V7BB104"))
      (libsource (lib "eagle-import") (part "CAP0402"))
    )
    (comp (ref "C717")
      (value "2u2")
      (footprint "eagle-import:0603-CAP")
      (fields (field (name "PARTNO") "C1608Y5V1C225Z"))
      (libsource (lib "eagle-import") (part "CAP0603"))
    )
    (comp (ref "D701")
      (value "DIODE-SCHOTTKY")
      (footprint "eagle-import:SOD-523")
      (fields (field (name "PARTNO") "MBRA140"))
      (libsource (lib "eagle-import") (part "DIODE-SCHOTTKY"))
    )
    (comp (ref "R701")
      (value "10K")
      (footprint "eagle-import:0402-RES")
      (fields (field (name "PARTNO") "RC0402FR-0710KL"))
      (libsource (lib "eagle-import") (part "RESISTOR0402-RES"))
    )
    (comp (ref "R702")
      (value "10K")
      (footprint "eagle-import:0402-RES")
      (fields (field (name "PARTNO") "RC0402FR-0710KL"))
      (libsource (lib "eagle-import") (part "RESISTOR0402-RES"))
    )
    (comp (ref "R703")
      (value "47K")
      (footprint "eagle-import:0402-RES")
      (fields (field (name "PARTNO") "RMCF0402FT47K"))
      (libsource (lib "eagle-import") (part "RESISTOR0402-RES"))
    )
    (comp (ref "R704")
      (value "10K")
      (footprint "eagle-import:0402-RES")
      (fields (field (name "PARTNO") "RC0402FR-0710KL"))
      (libsource (lib "eagle-import") (part "RESISTOR0402-RES"))
    )
    (comp (ref "R705")
      (value "10K")
      (footprint "eagle-import:0402-RES")
      (fields (field (name "PARTNO") "RC0402FR-0710KL"))
      (libsource (lib "eagle-import") (part "RESISTOR0402-RES"))
    )
    (comp (ref "R706")
      (value "1K")
      (footprint "eagle-import:0402-RES")
      (fields (field (name "PARTNO") "RC0402FR-071KL"))
      (libsource (lib "eagle-import") (part "RESISTOR0402-RES"))
    )
    (comp (ref "R707")
      (value "10K/0.1%")
      (footprint "eagle-import:0402-RES")
      (fields (field (name "PARTNO") "ERA-2AEB103X"))
      (libsource (lib "eagle-import") (part "RESISTOR0402-RES"))
    )
    (comp (ref "R708")
      (value "10K/0.1%")
      (footprint "eagle-import:0402-RES")
      (fields (field (name "PARTNO") "ERA-2AEB103X"))
      (libsource (lib "eagle-import") (part "RESISTOR0402-RES"))
    )
    (comp (ref "R709")
      (value "10K")
      (footprint "eagle-import:0402-RES")
      (fields (field (name "PARTNO") "RC0402FR-0710KL"))
      (libsource (lib "eagle-import") (part "RESISTOR0402-RES"))
    )
    (comp (ref "S701")
      (value "RESET")
      (footprint "eagle-import:EVQP7J01K")
      (fields (field (name "PARTNO") "EVQP7J01K"))
      (libsource (lib "eagle-import") (part "SWITCH-MOMENTARY-2"))
    )
    (comp (ref "U$701")
      (value "MIC5332")
      (footprint "eagle-import:MLF-8-EPAD")
      (fields (field (name "PARTNO") "MIC5332-SSYMT"))
      (libsource (lib "eagle-import") (part "MIC5332"))
    )
    (comp (ref "U$702")
      (value "MIC5332")
      (footprint "eagle-import:MLF-8-EPAD")
      (fields (field (name "PARTNO") "MIC5332-SSYMT"))
      (libsource (lib "eagle-import") (part "MIC5332"))
    )
    (comp (ref "U$703")
      (value "BQ24315")
      (footprint "eagle-import:QFN8-DSG")
      (fields (field (name "PARTNO") "BQ24315DSGR"))
      (libsource (lib "eagle-import") (part "BQ24315"))
    )
    (comp (ref "U$704")
      (value "MS621FE")
      (footprint "eagle-import:MS621FE")
      (libsource (lib "eagle-import") (part "MS621FE"))
    )
    (comp (ref "U101")
      (value "STM32F4X7VX")
      (footprint "eagle-import:TQFP100")
      (fields (field (name "PARTNO") "STM32F427VI"))
      (libsource (lib "eagle-import") (part "STM32F4X7VX"))
    )
    (comp (ref "C401")
      (value "0u1")
      (footprint "eagle-import:0402-CAP")
      (fields (field (name "PARTNO") "CC0402ZRY5V7BB104"))
      (libsource (lib "eagle-import") (part "CAP0402"))
    )
    (comp (ref "C402")
      (value "0u1")
      (footprint "eagle-import:0402-CAP")
      (fields (field (name "PARTNO") "CC0402ZRY5V7BB104"))
      (libsource (lib "eagle-import") (part "CAP0402"))
    )
    (comp (ref "C403")
      (value "0u1")
      (footprint "eagle-import:0402-CAP")
      (fields (field (name "PARTNO") "CC0402ZRY5V7BB104"))
      (libsource (lib "eagle-import") (part "CAP0402"))
    )
    (comp (ref "C404")
      (value "0u1")
      (footprint "eagle-import:0402-CAP")
      (fields (field (name "PARTNO") "CC0402ZRY5V7BB104"))
      (libsource (lib "eagle-import") (part "CAP0402"))
    )
    (comp (ref "J401")
      (value "M04X2")
      (footprint "eagle-import:2X4")
      (libsource (lib "eagle-import") (part "M04X2"))
    )
    (comp (ref "JP401")
      (value "M04PTH")
      (footprint "eagle-import:1X04")
      (libsource (lib "eagle-import") (part "M04PTH"))
    )
    (comp (ref "JP402")
      (value "M04PTH")
      (footprint "eagle-import:1X04")
      (libsource (lib "eagle-import") (part "M04PTH"))
    )
    (comp (ref "JP403")
      (value "M03PTH")
      (footprint "eagle-import:1X03")
      (fields (field (name "PARTNO") "EXCLUDE"))
      (libsource (lib "eagle-import") (part "M03PTH"))
    )
    (comp (ref "JP404")
      (value "M04PTH")
      (footprint "eagle-import:1X04")
      (libsource (lib "eagle-import") (part "M04PTH"))
    )
    (comp (ref "JP405")
      (value "M04PTH")
      (footprint "eagle-import:1X04")
      (libsource (lib "eagle-import") (part "M04PTH"))
    )
    (comp (ref "L401")
      (value "KNH16C104DA5TS")
      (footprint "eagle-import:KYOCERA-KNH16-DA")
      (libsource (lib "eagle-import") (part "KNH16C104DA5TS"))
    )
    (comp (ref "L402")
      (value "KNH16C104DA5TS")
      (footprint "eagle-import:KYOCERA-KNH16-DA")
      (libsource (lib "eagle-import") (part "KNH16C104DA5TS"))
    )
    (comp (ref "L403")
      (value "NUF8402MN")
      (footprint "eagle-import:DFN16-THIN")
      (fields (field (name "PARTNO") "NUF8402MN"))
      (libsource (lib "eagle-import") (part "NUF8402MN"))
    )
    (comp (ref "L404")
      (value "KNH16C104DA5TS")
      (footprint "eagle-import:KYOCERA-KNH16-DA")
      (libsource (lib "eagle-import") (part "KNH16C104DA5TS"))
    )
    (comp (ref "R401")
      (value "1K5")
      (footprint "eagle-import:0402-RES")
      (fields (field (name "PARTNO") "RC0402FR-071K5L"))
      (libsource (lib "eagle-import") (part "RESISTOR0402-RES"))
    )
    (comp (ref "R402")
      (value "1K5")
      (footprint "eagle-import:0402-RES")
      (fields (field (name "PARTNO") "RC0402FR-071K5L"))
      (libsource (lib "eagle-import") (part "RESISTOR0402-RES"))
    )
    (comp (ref "R403")
      (value "1K5")
      (footprint "eagle-import:0402-RES")
      (fields (field (name "PARTNO") "RC0402FR-071K5L"))
      (libsource (lib "eagle-import") (part "RESISTOR0402-RES"))
    )
    (comp (ref "R404")
      (value "1K5")
      (footprint "eagle-import:0402-RES")
      (fields (field (name "PARTNO") "RC0402FR-071K5L"))
      (libsource (lib "eagle-import") (part "RESISTOR0402-RES"))
    )
    (comp (ref "R405")
      (value "10K/0.1%")
      (footprint "eagle-import:0402-RES")
      (fields (field (name "PARTNO") "ERA-2AEB103X"))
      (libsource (lib "eagle-import") (part "RESISTOR0402-RES"))
    )
    (comp (ref "R406")
      (value "10K/0.1%")
      (footprint "eagle-import:0402-RES")
      (fields (field (name "PARTNO") "ERA-2AEB103X"))
      (libsource (lib "eagle-import") (part "RESISTOR0402-RES"))
    )
    (comp (ref "R407")
      (value "120R")
      (footprint "eagle-import:0402-RES")
      (fields (field (name "PARTNO") "RC0402FR-07120RL"))
      (libsource (lib "eagle-import") (part "RESISTOR0402-RES"))
    )
    (comp (ref "R408")
      (value "120R")
      (footprint "eagle-import:0402-RES")
      (fields (field (name "PARTNO") "RC0402FR-07120RL"))
      (libsource (lib "eagle-import") (part "RESISTOR0402-RES"))
    )
    (comp (ref "SJ401")
      (value "SOLDERJUMPERNC2")
      (footprint "eagle-import:SJ_2S-NOTRACE")
      (libsource (lib "eagle-import") (part "SOLDERJUMPERNC2"))
    )
    (comp (ref "SJ402")
      (value "SOLDERJUMPERNC2")
      (footprint "eagle-import:SJ_2S-NOTRACE")
      (libsource (lib "eagle-import") (part "SOLDERJUMPERNC2"))
    )
    (comp (ref "U$401")
      (value "PESD0402-140")
      (footprint "eagle-import:0402-TVS")
      (libsource (lib "eagle-import") (part "DIODE-TVS"))
    )
    (comp (ref "U$402")
      (value "PESD0402-140")
      (footprint "eagle-import:0402-TVS")
      (libsource (lib "eagle-import") (part "DIODE-TVS"))
    )
    (comp (ref "U401")
      (value "MAX3051")
      (footprint "eagle-import:SOT23-8")
      (fields (field (name "PARTNO") "MAX3051EKA"))
      (libsource (lib "eagle-import") (part "MAX3051MAX3051EKA"))
    )
    (comp (ref "U402")
      (value "MAX3051")
      (footprint "eagle-import:SOT23-8")
      (fields (field (name "PARTNO") "MAX3051EKA"))
      (libsource (lib "eagle-import") (part "MAX3051MAX3051EKA"))
    )
    (comp (ref "C501")
      (value "10u/10V")
      (footprint "eagle-import:0805-CAP")
      (fields (field (name "PARTNO") "CC0805ZKY5V6BB106"))
      (libsource (lib "eagle-import") (part "CAP0805"))
    )
    (comp (ref "C502")
      (value "10n")
      (footprint "eagle-import:0402-CAP")
      (fields (field (name "PARTNO") "CC0402KRX7R7BB103"))
      (libsource (lib "eagle-import") (part "CAP0402"))
    )
    (comp (ref "C503")
      (value "0u1")
      (footprint "eagle-import:0402-CAP")
      (fields (field (name "PARTNO") "CC0402ZRY5V7BB104"))
      (libsource (lib "eagle-import") (part "CAP0402"))
    )
    (comp (ref "U$501")
      (value "MAX21100")
      (footprint "eagle-import:16LGA-3X3")
      (fields (field (name "PARTNO") "MAX21100+"))
      (libsource (lib "eagle-import") (part "MAX21100"))
    )
    (comp (ref "JP801")
      (value "M03PTH")
      (footprint "eagle-import:1X03")
      (libsource (lib "eagle-import") (part "M03PTH"))
    )
    (comp (ref "LED801")
      (value "AMBER")
      (footprint "eagle-import:0603-LED")
      (fields (field (name "PARTNO") "APTD1608SECK"))
      (libsource (lib "eagle-import") (part "LED0603"))
    )
    (comp (ref "LED802")
      (value "GREEN")
      (footprint "eagle-import:0603-LED")
      (fields (field (name "PARTNO") "APTD1608CGCK"))
      (libsource (lib "eagle-import") (part "LED0603"))
    )
    (comp (ref "R801")
      (value "47R")
      (footprint "eagle-import:0402-RES")
      (fields (field (name "PARTNO") "RC0402JR-0747RL"))
      (libsource (lib "eagle-import") (part "RESISTOR0402-RES"))
    )
    (comp (ref "R802")
      (value "1K5")
      (footprint "eagle-import:0402-RES")
      (fields (field (name "PARTNO") "RC0402FR-071K5L"))
      (libsource (lib "eagle-import") (part "RESISTOR0402-RES"))
    )
    (comp (ref "R803")
      (value "220R")
      (footprint "eagle-import:0402-RES")
      (fields (field (name "PARTNO") "RC0402FR-07220RL"))
      (libsource (lib "eagle-import") (part "RESISTOR0402-RES"))
    )
    (comp (ref "R804")
      (value "220R")
      (footprint "eagle-import:0402-RES")
      (fields (field (name "PARTNO") "RC0402FR-07220RL"))
      (libsource (lib "eagle-import") (part "RESISTOR0402-RES"))
    )
    (comp (ref "R805")
      (value "220R")
      (footprint "eagle-import:0402-RES")
      (fields (field (name "PARTNO") "RC0402FR-07220RL"))
      (libsource (lib "eagle-import") (part "RESISTOR0402-RES"))
    )
    (comp (ref "U$801")
      (value "PESD0402-140")
      (footprint "eagle-import:0402-TVS")
      (libsource (lib "eagle-import") (part "DIODE-TVS"))
    )
    (comp (ref "J1001")
      (value "SERVO_HEADER-3X8")
      (footprint "eagle-import:3X8RA_SERVO")
      (fields (field (name "BOM") "EXCLUDE"))
      (libsource (lib "eagle-import") (part "SERVO_HEADER-3X8"))
    )
    (comp (ref "JP1001")
      (value "M01SMD-4.5X1.5")
      (footprint "eagle-import:PAD-1.5X4.5")
      (libsource (lib "eagle-import") (part "M01SMD-4.5X1.5"))
    )
    (comp (ref "JP1002")
      (value "M01SMD-4.5X1.5")
      (footprint "eagle-import:PAD-1.5X4.5")
      (libsource (lib "eagle-import") (part "M01SMD-4.5X1.5"))
    )
    (comp (ref "L1001")
      (value "NUF8402MN")
      (footprint "eagle-import:DFN16-THIN")
      (fields (field (name "PARTNO") "NUF8402MN"))
      (libsource (lib "eagle-import") (part "NUF8402MN"))
    )
    (comp (ref "R1001")
      (value "220R")
      (footprint "eagle-import:0402-RES")
      (fields (field (name "PARTNO") "RC0402FR-07220RL"))
      (libsource (lib "eagle-import") (part "RESISTOR0402-RES"))
    )
    (comp (ref "R1002")
      (value "220R")
      (footprint "eagle-import:0402-RES")
      (fields (field (name "PARTNO") "RC0402FR-07220RL"))
      (libsource (lib "eagle-import") (part "RESISTOR0402-RES"))
    )
    (comp (ref "C101")
      (value "16p")
      (footprint "eagle-import:0402-CAP")
      (fields (field (name "PARTNO") "C1005C0G1H160"))
      (libsource (lib "eagle-import") (part "CAP0402"))
    )
    (comp (ref "C102")
      (value "16p")
      (footprint "eagle-import:0402-CAP")
      (fields (field (name "PARTNO") "C1005C0G1H160"))
      (libsource (lib "eagle-import") (part "CAP0402"))
    )
    (comp (ref "R101")
      (value "10K")
      (footprint "eagle-import:0402-RES")
      (fields (field (name "PARTNO") "RC0402FR-0710KL"))
      (libsource (lib "eagle-import") (part "RESISTOR0402-RES"))
    )
    (comp (ref "X101")
      (value "3.2x2.5 mm / 24 MHz / 30 ppm / 10pF")
      (footprint "eagle-import:OSCILLATOR-3.2X2.5")
      (fields (field (name "PARTNO") "ABM8G-24.000MHZ-4Y-T3"))
      (libsource (lib "eagle-import") (part "OSCILLATOR-3.2X2.5"))
    )
    (comp (ref "JP1101")
      (value "FIDUCIAL1.5X3")
      (footprint "eagle-import:FIDUCIAL-1.5X3")
      (libsource (lib "eagle-import") (part "FIDUCIAL1.5X3"))
    )
    (comp (ref "JP1102")
      (value "FIDUCIAL1.5X3")
      (footprint "eagle-import:FIDUCIAL-1.5X3")
      (libsource (lib "eagle-import") (part "FIDUCIAL1.5X3"))
    )
    (comp (ref "JP1103")
      (value "FIDUCIAL1.5X3")
      (footprint "eagle-import:FIDUCIAL-1.5X3")
      (libsource (lib "eagle-import") (part "FIDUCIAL1.5X3"))
    )
    (comp (ref "JP1104")
      (value "FIDUCIAL1.5X3")
      (footprint "eagle-import:FIDUCIAL-1.5X3")
      (libsource (lib "eagle-import") (part "FIDUCIAL1.5X3"))
    )
    (comp (ref "JP1105")
      (value "M01PTH")
      (footprint "eagle-import:1X01")
      (libsource (lib "eagle-import") (part "M01PTH"))
    )
    (comp (ref "M3_MOUNT1101")
      (value "MOUNT-HOLE3.1MM")
      (footprint "eagle-import:MOUNT-HOLE3.1")
      (libsource (lib "eagle-import") (part "MOUNT-HOLE3.1MM"))
    )
    (comp (ref "M3_MOUNT1102")
      (value "MOUNT-HOLE3.1MM")
      (footprint "eagle-import:MOUNT-HOLE3.1")
      (libsource (lib "eagle-import") (part "MOUNT-HOLE3.1MM"))
    )
    (comp (ref "M3_MOUNT1103")
      (value "MOUNT-HOLE3.1MM")
      (footprint "eagle-import:MOUNT-HOLE3.1")
      (libsource (lib "eagle-import") (part "MOUNT-HOLE3.1MM"))
    )
    (comp (ref "M3_MOUNT1104")
      (value "MOUNT-HOLE3.1MM")
      (footprint "eagle-import:MOUNT-HOLE3.1")
      (libsource (lib "eagle-import") (part "MOUNT-HOLE3.1MM"))
    )
    (comp (ref "OSHW_LOGO")
      (value "OSHW-LOGOS")
      (footprint "eagle-import:OSHW-LOGO-S")
      (libsource (lib "eagle-import") (part "OSHW-LOGOS"))
    )
  )
  (nets
    (net (code "1") (name "ACCEL_DRDY") (class "Default")
      (node (ref "U$501") (pin "11") (pinfunction "INT1_11") (pintype "bidirectional"))
      (node (ref "U101") (pin "90") (pinfunction "PB4_90") (pintype "bidirectional"))
    )
    (net (code "2") (name "ALARM") (class "Default")
      (node (ref "U101") (pin "77") (pinfunction "PA15_77") (pintype "bidirectional"))
    )
    (net (code "3") (name "CAN1_H") (class "Default")
      (node (ref "JP405") (pin "2") (pinfunction "2_2") (pintype "passive"))
      (node (ref "R407") (pin "P$1") (pinfunction "1_P$1") (pintype "passive"))
      (node (ref "U402") (pin "7") (pinfunction "CANH_7") (pintype "bidirectional"))
    )
    (net (code "4") (name "CAN1_L") (class "Default")
      (node (ref "JP405") (pin "3") (pinfunction "3_3") (pintype "passive"))
      (node (ref "SJ402") (pin "2") (pinfunction "2_2") (pintype "passive"))
      (node (ref "U402") (pin "6") (pinfunction "CANL_6") (pintype "bidirectional"))
    )
    (net (code "5") (name "CAN1_RX") (class "Default")
      (node (ref "U101") (pin "81") (pinfunction "PD0_81") (pintype "bidirectional"))
      (node (ref "U402") (pin "4") (pinfunction "DOUT_4") (pintype "output"))
    )
    (net (code "6") (name "CAN1_TX") (class "Default")
      (node (ref "U101") (pin "82") (pinfunction "PD1_82") (pintype "bidirectional"))
      (node (ref "U402") (pin "1") (pinfunction "DIN_1") (pintype "input"))
    )
    (net (code "7") (name "CAN2_RX") (class "Default")
      (node (ref "U101") (pin "51") (pinfunction "PB12_51") (pintype "bidirectional"))
      (node (ref "U401") (pin "4") (pinfunction "DOUT_4") (pintype "output"))
    )
    (net (code "8") (name "CAN2_TX") (class "Default")
      (node (ref "U101") (pin "92") (pinfunction "PB6_92") (pintype "bidirectional"))
      (node (ref "U401") (pin "1") (pinfunction "DIN_1") (pintype "input"))
    )
    (net (code "9") (name "FMU-BOOT0") (class "Default")
      (node (ref "JP1105") (pin "1") (pinfunction "1_1") (pintype "passive"))
      (node (ref "R709") (pin "P$2") (pinfunction "2_P$2") (pintype "passive"))
      (node (ref "U101") (pin "94") (pinfunction "BOOT0_94") (pintype "input"))
    )
    (net (code "10") (name "FMU-CH1") (class "Default")
      (node (ref "L1001") (pin "P$4") (pinfunction "P$1_P$4") (pintype "bidirectional"))
      (node (ref "U101") (pin "45") (pinfunction "PE14_45") (pintype "bidirectional"))
    )
    (net (code "11") (name "FMU-CH2") (class "Default")
      (node (ref "L1001") (pin "P$5") (pinfunction "P$1_P$5") (pintype "bidirectional"))
      (node (ref "U101") (pin "44") (pinfunction "PE13_44") (pintype "bidirectional"))
    )
    (net (code "12") (name "FMU-CH3") (class "Default")
      (node (ref "L1001") (pin "P$6") (pinfunction "P$1_P$6") (pintype "bidirectional"))
      (node (ref "U101") (pin "42") (pinfunction "PE11_42") (pintype "bidirectional"))
    )
    (net (code "13") (name "FMU-CH4") (class "Default")
      (node (ref "L1001") (pin "P$7") (pinfunction "P$1_P$7") (pintype "bidirectional"))
      (node (ref "U101") (pin "40") (pinfunction "PE9_40") (pintype "bidirectional"))
    )
    (net (code "14") (name "FMU-CH5") (class "Default")
      (node (ref "L1001") (pin "P$2") (pinfunction "P$1_P$2") (pintype "bidirectional"))
      (node (ref "U101") (pin "60") (pinfunction "PD13_60") (pintype "bidirectional"))
    )
    (net (code "15") (name "FMU-CH6") (class "Default")
      (node (ref "L1001") (pin "P$3") (pinfunction "P$1_P$3") (pintype "bidirectional"))
      (node (ref "U101") (pin "62") (pinfunction "PD15_62") (pintype "bidirectional"))
    )
    (net (code "16") (name "FMU-CH7") (class "Default")
      (node (ref "L1001") (pin "P$8") (pinfunction "P$1_P$8") (pintype "bidirectional"))
      (node (ref "U101") (pin "24") (pinfunction "PA1_24") (pintype "bidirectional"))
    )
    (net (code "17") (name "FMU-CH8") (class "Default")
      (node (ref "L1001") (pin "P$1") (pinfunction "P$1_P$1") (pintype "bidirectional"))
      (node (ref "U$203") (pin "3") (pinfunction "2Y_3") (pintype "bidirectional"))
      (node (ref "U101") (pin "61") (pinfunction "PD14_61") (pintype "bidirectional"))
    )
    (net (code "18") (name "FMU-CH9") (class "Default")
      (node (ref "R1001") (pin "P$2") (pinfunction "2_P$2") (pintype "passive"))
      (node (ref "U101") (pin "25") (pinfunction "PA2_25") (pintype "bidirectional"))
    )
    (net (code "19") (name "FMU-CH10") (class "Default")
      (node (ref "R1002") (pin "P$2") (pinfunction "2_P$2") (pintype "passive"))
      (node (ref "U101") (pin "26") (pinfunction "PA3_26") (pintype "bidirectional"))
    )
    (net (code "20") (name "FMU-I2C1_SCL") (class "Default")
      (node (ref "L403") (pin "P$2") (pinfunction "P$1_P$2") (pintype "bidirectional"))
      (node (ref "R402") (pin "P$1") (pinfunction "1_P$1") (pintype "passive"))
      (node (ref "U101") (pin "95") (pinfunction "PB8_95") (pintype "bidirectional"))
    )
    (net (code "21") (name "FMU-I2C1_SDA") (class "Default")
      (node (ref "L403") (pin "P$7") (pinfunction "P$1_P$7") (pintype "bidirectional"))
      (node (ref "R404") (pin "P$1") (pinfunction "1_P$1") (pintype "passive"))
      (node (ref "U101") (pin "96") (pinfunction "PB9_96") (pintype "bidirectional"))
    )
    (net (code "22") (name "FMU-I2C2_SCL") (class "Default")
      (node (ref "L403") (pin "P$4") (pinfunction "P$1_P$4") (pintype "bidirectional"))
      (node (ref "R401") (pin "P$1") (pinfunction "1_P$1") (pintype "passive"))
      (node (ref "U101") (pin "47") (pinfunction "PB10_47") (pintype "bidirectional"))
    )
    (net (code "23") (name "FMU-I2C2_SDA") (class "Default")
      (node (ref "L403") (pin "P$8") (pinfunction "P$1_P$8") (pintype "bidirectional"))
      (node (ref "R403") (pin "P$1") (pinfunction "1_P$1") (pintype "passive"))
      (node (ref "U101") (pin "48") (pinfunction "PB11_48") (pintype "bidirectional"))
    )
    (net (code "24") (name "FMU-LED_SAFETY") (class "Default")
      (node (ref "R801") (pin "P$2") (pinfunction "2_P$2") (pintype "passive"))
      (node (ref "U101") (pin "9") (pinfunction "PC15_9") (pintype "bidirectional"))
    )
    (net (code "25") (name "FMU-SWCLK") (class "Default")
      (node (ref "JX301") (pin "4") (pinfunction "S_4") (pintype "passive"))
      (node (ref "U101") (pin "76") (pinfunction "PA14_76") (pintype "bidirectional"))
    )
    (net (code "26") (name "FMU-SWDIO") (class "Default")
      (node (ref "JX301") (pin "2") (pinfunction "S_2") (pintype "passive"))
      (node (ref "U101") (pin "72") (pinfunction "PA13_72") (pintype "bidirectional"))
    )
    (net (code "27") (name "FMU-SWO") (class "Default")
      (node (ref "JX301") (pin "6") (pinfunction "S_6") (pintype "passive"))
      (node (ref "U101") (pin "89") (pinfunction "PB3_89") (pintype "bidirectional"))
    )
    (net (code "28") (name "FMU-UART7_RX") (class "Default")
      (node (ref "L202") (pin "P$8") (pinfunction "P$1_P$8") (pintype "bidirectional"))
      (node (ref "U101") (pin "38") (pinfunction "PE7_38") (pintype "bidirectional"))
    )
    (net (code "29") (name "FMU-UART7_TX") (class "Default")
      (node (ref "L202") (pin "P$6") (pinfunction "P$1_P$6") (pintype "bidirectional"))
      (node (ref "U101") (pin "39") (pinfunction "PE8_39") (pintype "bidirectional"))
    )
    (net (code "30") (name "FMU-UART8_RX") (class "Default")
      (node (ref "U$203") (pin "6") (pinfunction "1Y_6") (pintype "bidirectional"))
      (node (ref "U101") (pin "97") (pinfunction "PE0_97") (pintype "bidirectional"))
    )
    (net (code "31") (name "FMU-UART8_TX") (class "Default")
      (node (ref "U$203") (pin "5") (pinfunction "2A_5") (pintype "bidirectional"))
      (node (ref "U101") (pin "98") (pinfunction "PE1_98") (pintype "bidirectional"))
    )
    (net (code "32") (name "FMU-USART2_CTS") (class "Default")
      (node (ref "L201") (pin "P$1") (pinfunction "P$1_P$1") (pintype "bidirectional"))
      (node (ref "U101") (pin "84") (pinfunction "PD3_84") (pintype "bidirectional"))
    )
    (net (code "33") (name "FMU-USART2_RTS") (class "Default")
      (node (ref "L201") (pin "P$2") (pinfunction "P$1_P$2") (pintype "bidirectional"))
      (node (ref "U101") (pin "85") (pinfunction "PD4_85") (pintype "bidirectional"))
    )
    (net (code "34") (name "FMU-USART2_RX") (class "Default")
      (node (ref "L201") (pin "P$4") (pinfunction "P$1_P$4") (pintype "bidirectional"))
      (node (ref "U101") (pin "87") (pinfunction "PD6_87") (pintype "bidirectional"))
    )
    (net (code "35") (name "FMU-USART2_TX") (class "Default")
      (node (ref "L201") (pin "P$3") (pinfunction "P$1_P$3") (pintype "bidirectional"))
      (node (ref "U101") (pin "86") (pinfunction "PD5_86") (pintype "bidirectional"))
    )
    (net (code "36") (name "FMU-USART3_CTS") (class "Default")
      (node (ref "L201") (pin "P$7") (pinfunction "P$1_P$7") (pintype "bidirectional"))
      (node (ref "U101") (pin "58") (pinfunction "PD11_58") (pintype "bidirectional"))
    )
    (net (code "37") (name "FMU-USART3_RTS") (class "Default")
      (node (ref "L201") (pin "P$8") (pinfunction "P$1_P$8") (pintype "bidirectional"))
      (node (ref "U101") (pin "59") (pinfunction "PD12_59") (pintype "bidirectional"))
    )
    (net (code "38") (name "FMU-USART3_RX") (class "Default")
      (node (ref "L201") (pin "P$6") (pinfunction "P$1_P$6") (pintype "bidirectional"))
      (node (ref "U101") (pin "56") (pinfunction "PD9_56") (pintype "bidirectional"))
    )
    (net (code "39") (name "FMU-USART3_TX") (class "Default")
      (node (ref "L201") (pin "P$5") (pinfunction "P$1_P$5") (pintype "bidirectional"))
      (node (ref "U101") (pin "55") (pinfunction "PD8_55") (pintype "bidirectional"))
    )
    (net (code "40") (name "FMU-VDD_3V3") (class "Default")
      (node (ref "C201") (pin "P$1") (pinfunction "1_P$1") (pintype "passive"))
      (node (ref "C301") (pin "P$1") (pinfunction "1_P$1") (pintype "passive"))
      (node (ref "C302") (pin "P$1") (pinfunction "1_P$1") (pintype "passive"))
      (node (ref "C401") (pin "P$1") (pinfunction "1_P$1") (pintype "passive"))
      (node (ref "C402") (pin "P$1") (pinfunction "1_P$1") (pintype "passive"))
      (node (ref "C705") (pin "P$1") (pinfunction "1_P$1") (pintype "passive"))
      (node (ref "C706") (pin "P$1") (pinfunction "1_P$1") (pintype "passive"))
      (node (ref "C709") (pin "P$1") (pinfunction "1_P$1") (pintype "passive"))
      (node (ref "C710") (pin "P$1") (pinfunction "1_P$1") (pintype "passive"))
      (node (ref "C711") (pin "P$1") (pinfunction "1_P$1") (pintype "passive"))
      (node (ref "C712") (pin "P$1") (pinfunction "1_P$1") (pintype "passive"))
      (node (ref "C714") (pin "P$1") (pinfunction "1_P$1") (pintype "passive"))
      (node (ref "C716") (pin "P$1") (pinfunction "1_P$1") (pintype "passive"))
      (node (ref "D701") (pin "A") (pinfunction "A_A") (pintype "passive"))
      (node (ref "JP801") (pin "1") (pinfunction "1_1") (pintype "passive"))
      (node (ref "JX301") (pin "1") (pinfunction "S_1") (pintype "passive"))
      (node (ref "R401") (pin "P$2") (pinfunction "2_P$2") (pintype "passive"))
      (node (ref "R402") (pin "P$2") (pinfunction "2_P$2") (pintype "passive"))
      (node (ref "R403") (pin "P$2") (pinfunction "2_P$2") (pintype "passive"))
      (node (ref "R404") (pin "P$2") (pinfunction "2_P$2") (pintype "passive"))
      (node (ref "R702") (pin "P$1") (pinfunction "1_P$1") (pintype "passive"))
      (node (ref "R704") (pin "P$1") (pinfunction "1_P$1") (pintype "passive"))
      (node (ref "R705") (pin "P$1") (pinfunction "1_P$1") (pintype "passive"))
      (node (ref "U$203") (pin "8") (pinfunction "VCC_8") (pintype "power_in"))
      (node (ref "U$302") (pin "8") (pinfunction "VCC_8") (pintype "bidirectional"))
      (node (ref "U$701") (pin "7") (pinfunction "VOUT2_7") (pintype "bidirectional"))
      (node (ref "U$801") (pin "C") (pinfunction "C_C") (pintype "passive"))
      (node (ref "U101") (pin "100") (pinfunction "VDD_100") (pintype "power_in"))
      (node (ref "U101") (pin "11") (pinfunction "VDD_11") (pintype "power_in"))
      (node (ref "U101") (pin "19") (pinfunction "VDD_19") (pintype "power_in"))
      (node (ref "U101") (pin "21") (pinfunction "VREF+_21") (pintype "input"))
      (node (ref "U101") (pin "22") (pinfunction "VDDA_22") (pintype "power_in"))
      (node (ref "U101") (pin "28") (pinfunction "VDD_28") (pintype "power_in"))
      (node (ref "U101") (pin "50") (pinfunction "VDD_50") (pintype "power_in"))
      (node (ref "U101") (pin "75") (pinfunction "VDD_75") (pintype "power_in"))
      (node (ref "U401") (pin "3") (pinfunction "VCC_3") (pintype "input"))
      (node (ref "U402") (pin "3") (pinfunction "VCC_3") (pintype "input"))
    )
    (net (code "41") (name "FMU-~{RESET}") (class "Default")
      (node (ref "C713") (pin "P$2") (pinfunction "2_P$2") (pintype "passive"))
      (node (ref "JX301") (pin "10") (pinfunction "S_10") (pintype "passive"))
      (node (ref "S701") (pin "A1") (pinfunction "1_A1") (pintype "passive"))
      (node (ref "U$701") (pin "3") (pinfunction "POR2_3") (pintype "bidirectional"))
      (node (ref "U101") (pin "14") (pinfunction "NRST_14") (pintype "input"))
    )
    (net (code "42") (name "FMU_AUX_ADC1") (class "Default")
      (node (ref "R405") (pin "P$1") (pinfunction "1_P$1") (pintype "passive"))
      (node (ref "U101") (pin "18") (pinfunction "PC3_18") (pintype "bidirectional"))
    )
    (net (code "43") (name "FMU_AUX_ADC2") (class "Default")
      (node (ref "R406") (pin "P$1") (pinfunction "1_P$1") (pintype "passive"))
      (node (ref "U101") (pin "33") (pinfunction "PC4_33") (pintype "bidirectional"))
    )
    (net (code "44") (name "FRAM_MISO") (class "Default")
      (node (ref "U101") (pin "53") (pinfunction "PB14_53") (pintype "bidirectional"))
    )
    (net (code "45") (name "FRAM_MOSI") (class "Default")
      (node (ref "U101") (pin "54") (pinfunction "PB15_54") (pintype "bidirectional"))
    )
    (net (code "46") (name "FRAM_SCK") (class "Default")
      (node (ref "U101") (pin "52") (pinfunction "PB13_52") (pintype "bidirectional"))
    )
    (net (code "47") (name "GND") (class "Default")
      (node (ref "C101") (pin "P$2") (pinfunction "2_P$2") (pintype "passive"))
      (node (ref "C102") (pin "P$1") (pinfunction "1_P$1") (pintype "passive"))
      (node (ref "C201") (pin "P$2") (pinfunction "2_P$2") (pintype "passive"))
      (node (ref "C301") (pin "P$2") (pinfunction "2_P$2") (pintype "passive"))
      (node (ref "C302") (pin "P$2") (pinfunction "2_P$2") (pintype "passive"))
      (node (ref "C401") (pin "P$2") (pinfunction "2_P$2") (pintype "passive"))
      (node (ref "C402") (pin "P$2") (pinfunction "2_P$2") (pintype "passive"))
      (node (ref "C403") (pin "P$2") (pinfunction "2_P$2") (pintype "passive"))
      (node (ref "C404") (pin "P$2") (pinfunction "2_P$2") (pintype "passive"))
      (node (ref "C501") (pin "P$2") (pinfunction "2_P$2") (pintype "passive"))
      (node (ref "C502") (pin "P$2") (pinfunction "2_P$2") (pintype "passive"))
      (node (ref "C503") (pin "P$2") (pinfunction "2_P$2") (pintype "passive"))
      (node (ref "C601") (pin "2") (pinfunction "2_2") (pintype "passive"))
      (node (ref "C602") (pin "P$2") (pinfunction "2_P$2") (pintype "passive"))
      (node (ref "C603") (pin "P$2") (pinfunction "2_P$2") (pintype "passive"))
      (node (ref "C604") (pin "2") (pinfunction "2_2") (pintype "passive"))
      (node (ref "C605") (pin "2") (pinfunction "2_2") (pintype "passive"))
      (node (ref "C606") (pin "2") (pinfunction "2_2") (pintype "passive"))
      (node (ref "C701") (pin "P$2") (pinfunction "2_P$2") (pintype "passive"))
      (node (ref "C702") (pin "P$2") (pinfunction "2_P$2") (pintype "passive"))
      (node (ref "C703") (pin "P$1") (pinfunction "1_P$1") (pintype "passive"))
      (node (ref "C704") (pin "P$2") (pinfunction "2_P$2") (pintype "passive"))
      (node (ref "C705") (pin "P$2") (pinfunction "2_P$2") (pintype "passive"))
      (node (ref "C706") (pin "P$2") (pinfunction "2_P$2") (pintype "passive"))
      (node (ref "C707") (pin "P$2") (pinfunction "2_P$2") (pintype "passive"))
      (node (ref "C708") (pin "P$2") (pinfunction "2_P$2") (pintype "passive"))
      (node (ref "C709") (pin "P$2") (pinfunction "2_P$2") (pintype "passive"))
      (node (ref "C710") (pin "P$2") (pinfunction "2_P$2") (pintype "passive"))
      (node (ref "C711") (pin "P$2") (pinfunction "2_P$2") (pintype "passive"))
      (node (ref "C712") (pin "P$2") (pinfunction "2_P$2") (pintype "passive"))
      (node (ref "C713") (pin "P$1") (pinfunction "1_P$1") (pintype "passive"))
      (node (ref "C714") (pin "P$2") (pinfunction "2_P$2") (pintype "passive"))
      (node (ref "C715") (pin "P$2") (pinfunction "2_P$2") (pintype "passive"))
      (node (ref "C716") (pin "P$2") (pinfunction "2_P$2") (pintype "passive"))
      (node (ref "C717") (pin "P$2") (pinfunction "2_P$2") (pintype "passive"))
      (node (ref "D901") (pin "A") (pinfunction "A_A") (pintype "passive"))
      (node (ref "J1001") (pin "GND_S1") (pinfunction "S_GND_S1") (pintype "passive"))
      (node (ref "J1001") (pin "GND_S2") (pinfunction "S_GND_S2") (pintype "passive"))
      (node (ref "J1001") (pin "GND_S3") (pinfunction "S_GND_S3") (pintype "passive"))
      (node (ref "J1001") (pin "GND_S4") (pinfunction "S_GND_S4") (pintype "passive"))
      (node (ref "J1001") (pin "GND_S5") (pinfunction "S_GND_S5") (pintype "passive"))
      (node (ref "J1001") (pin "GND_S6") (pinfunction "S_GND_S6") (pintype "passive"))
      (node (ref "J1001") (pin "GND_S7") (pinfunction "S_GND_S7") (pintype "passive"))
      (node (ref "J1001") (pin "GND_S8") (pinfunction "S_GND_S8") (pintype "passive"))
      (node (ref "J401") (pin "7") (pinfunction "7_7") (pintype "passive"))
      (node (ref "JP202") (pin "3") (pinfunction "3_3") (pintype "bidirectional"))
      (node (ref "JP203") (pin "5") (pinfunction "5_5") (pintype "bidirectional"))
      (node (ref "JP204") (pin "5") (pinfunction "5_5") (pintype "bidirectional"))
      (node (ref "JP205") (pin "5") (pinfunction "5_5") (pintype "bidirectional"))
      (node (ref "JP301") (pin "4") (pinfunction "4_4") (pintype "passive"))
      (node (ref "JP401") (pin "4") (pinfunction "4_4") (pintype "passive"))
      (node (ref "JP402") (pin "4") (pinfunction "4_4") (pintype "passive"))
      (node (ref "JP403") (pin "3") (pinfunction "3_3") (pintype "passive"))
      (node (ref "JP404") (pin "4") (pinfunction "4_4") (pintype "passive"))
      (node (ref "JP405") (pin "4") (pinfunction "4_4") (pintype "passive"))
      (node (ref "JP901") (pin "2") (pinfunction "2_2") (pintype "passive"))
      (node (ref "JX301") (pin "3") (pinfunction "S_3") (pintype "passive"))
      (node (ref "JX301") (pin "5") (pinfunction "S_5") (pintype "passive"))
      (node (ref "JX301") (pin "9") (pinfunction "S_9") (pintype "passive"))
      (node (ref "L1001") (pin "P$EP") (pinfunction "GND_P$EP") (pintype "power_in"))
      (node (ref "L201") (pin "P$EP") (pinfunction "GND_P$EP") (pintype "power_in"))
      (node (ref "L202") (pin "P$EP") (pinfunction "GND_P$EP") (pintype "power_in"))
      (node (ref "L203") (pin "P$3") (pinfunction "P$3_P$3") (pintype "bidirectional"))
      (node (ref "L203") (pin "P$4") (pinfunction "P$3_P$4") (pintype "bidirectional"))
      (node (ref "L203") (pin "P$5") (pinfunction "P$3_P$5") (pintype "bidirectional"))
      (node (ref "L401") (pin "P$3") (pinfunction "P$3_P$3") (pintype "bidirectional"))
      (node (ref "L401") (pin "P$4") (pinfunction "P$3_P$4") (pintype "bidirectional"))
      (node (ref "L401") (pin "P$5") (pinfunction "P$3_P$5") (pintype "bidirectional"))
      (node (ref "L402") (pin "P$3") (pinfunction "P$3_P$3") (pintype "bidirectional"))
      (node (ref "L402") (pin "P$4") (pinfunction "P$3_P$4") (pintype "bidirectional"))
      (node (ref "L402") (pin "P$5") (pinfunction "P$3_P$5") (pintype "bidirectional"))
      (node (ref "L403") (pin "P$EP") (pinfunction "GND_P$EP") (pintype "power_in"))
      (node (ref "L404") (pin "P$3") (pinfunction "P$3_P$3") (pintype "bidirectional"))
      (node (ref "L404") (pin "P$4") (pinfunction "P$3_P$4") (pintype "bidirectional"))
      (node (ref "L404") (pin "P$5") (pinfunction "P$3_P$5") (pintype "bidirectional"))
      (node (ref "R101") (pin "P$2") (pinfunction "2_P$2") (pintype "passive"))
      (node (ref "R203") (pin "P$2") (pinfunction "2_P$2") (pintype "passive"))
      (node (ref "R204") (pin "P$1") (pinfunction "1_P$1") (pintype "passive"))
      (node (ref "R701") (pin "P$1") (pinfunction "1_P$1") (pintype "passive"))
      (node (ref "R703") (pin "P$2") (pinfunction "2_P$2") (pintype "passive"))
      (node (ref "R708") (pin "P$2") (pinfunction "2_P$2") (pintype "passive"))
      (node (ref "R709") (pin "P$1") (pinfunction "1_P$1") (pintype "passive"))
      (node (ref "R802") (pin "P$2") (pinfunction "2_P$2") (pintype "passive"))
      (node (ref "R805") (pin "P$1") (pinfunction "1_P$1") (pintype "passive"))
      (node (ref "R903") (pin "P$1") (pinfunction "1_P$1") (pintype "passive"))
      (node (ref "S701") (pin "B3") (pinfunction "2_B3") (pintype "passive"))
      (node (ref "U$201") (pin "A") (pinfunction "A_A") (pintype "passive"))
      (node (ref "U$202") (pin "A") (pinfunction "A_A") (pintype "passive"))
      (node (ref "U$203") (pin "1") (pinfunction "~{1OE}_1") (pintype "input"))
      (node (ref "U$203") (pin "4") (pinfunction "GND_4") (pintype "power_in"))
      (node (ref "U$204") (pin "A") (pinfunction "A_A") (pintype "passive"))
      (node (ref "U$301") (pin "2") (pinfunction "GND_2") (pintype "bidirectional"))
      (node (ref "U$302") (pin "4") (pinfunction "GND_4") (pintype "bidirectional"))
      (node (ref "U$302") (pin "PAD") (pinfunction "GND_PAD") (pintype "bidirectional"))
      (node (ref "U$401") (pin "A") (pinfunction "A_A") (pintype "passive"))
      (node (ref "U$402") (pin "A") (pinfunction "A_A") (pintype "passive"))
      (node (ref "U$501") (pin "10") (pinfunction "RSV1_10") (pintype "input"))
      (node (ref "U$501") (pin "5") (pinfunction "GND_5") (pintype "power_in"))
      (node (ref "U$601") (pin "11") (pinfunction "GND_11") (pintype "power_in"))
      (node (ref "U$601") (pin "15") (pinfunction "PGND_15") (pintype "power_in"))
      (node (ref "U$601") (pin "16") (pinfunction "PGND_16") (pintype "power_in"))
      (node (ref "U$601") (pin "17") (pinfunction "PGND_17") (pintype "power_in"))
      (node (ref "U$601") (pin "18") (pinfunction "PGND_18") (pintype "power_in"))
      (node (ref "U$601") (pin "19") (pinfunction "PGND_19") (pintype "power_in"))
      (node (ref "U$601") (pin "20") (pinfunction "PGND_20") (pintype "power_in"))
      (node (ref "U$601") (pin "21") (pinfunction "PGND_21") (pintype "power_in"))
      (node (ref "U$601") (pin "22") (pinfunction "PGND_22") (pintype "power_in"))
      (node (ref "U$601") (pin "23") (pinfunction "PGND_23") (pintype "power_in"))
      (node (ref "U$601") (pin "4") (pinfunction "PS/SYNC_4") (pintype "input"))
      (node (ref "U$601") (pin "6") (pinfunction "PGND_6") (pintype "power_in"))
      (node (ref "U$601") (pin "7") (pinfunction "PGND_7") (pintype "power_in"))
      (node (ref "U$601") (pin "8") (pinfunction "PGND_8") (pintype "power_in"))
      (node (ref "U$601") (pin "9") (pinfunction "PGND_9") (pintype "power_in"))
      (node (ref "U$601") (pin "EP") (pinfunction "PGND_EP") (pintype "power_in"))
      (node (ref "U$601") (pin "EP1") (pinfunction "PGND_EP1") (pintype "power_in"))
      (node (ref "U$701") (pin "2") (pinfunction "GND_2") (pintype "bidirectional"))
      (node (ref "U$701") (pin "GND") (pinfunction "GND_GND") (pintype "bidirectional"))
      (node (ref "U$702") (pin "2") (pinfunction "GND_2") (pintype "bidirectional"))
      (node (ref "U$702") (pin "4") (pinfunction "EN2_4") (pintype "bidirectional"))
      (node (ref "U$702") (pin "GND") (pinfunction "GND_GND") (pintype "bidirectional"))
      (node (ref "U$703") (pin "2") (pinfunction "VSS_2") (pintype "bidirectional"))
      (node (ref "U$703") (pin "6") (pinfunction "VBAT_6") (pintype "bidirectional"))
      (node (ref "U$703") (pin "GND") (pinfunction "VSS_GND") (pintype "bidirectional"))
      (node (ref "U$703") (pin "P$2") (pinfunction "VSS_P$2") (pintype "bidirectional"))
      (node (ref "U$703") (pin "P$3") (pinfunction "VSS_P$3") (pintype "bidirectional"))
      (node (ref "U$704") (pin "2") (pinfunction "NEG_2") (pintype "bidirectional"))
      (node (ref "U$801") (pin "A") (pinfunction "A_A") (pintype "passive"))
      (node (ref "U101") (pin "10") (pinfunction "VSS_10") (pintype "power_in"))
      (node (ref "U101") (pin "20") (pinfunction "VSSA_20") (pintype "power_in"))
      (node (ref "U101") (pin "27") (pinfunction "VSS_27") (pintype "power_in"))
      (node (ref "U101") (pin "74") (pinfunction "VSS_74") (pintype "power_in"))
      (node (ref "U101") (pin "99") (pinfunction "VSS_99") (pintype "power_in"))
      (node (ref "U401") (pin "2") (pinfunction "GND_2") (pintype "power_in"))
      (node (ref "U401") (pin "5") (pinfunction "SHDN_5") (pintype "input"))
      (node (ref "U401") (pin "8") (pinfunction "RS_8") (pintype "input"))
      (node (ref "U402") (pin "2") (pinfunction "GND_2") (pintype "power_in"))
      (node (ref "U402") (pin "5") (pinfunction "SHDN_5") (pintype "input"))
      (node (ref "U402") (pin "8") (pinfunction "RS_8") (pintype "input"))
      (node (ref "X101") (pin "2") (pinfunction "NC_2_2") (pintype "power_in"))
      (node (ref "X101") (pin "4") (pinfunction "NC_4_4") (pintype "power_in"))
    )
    (net (code "48") (name "GPIO_EXT_1") (class "Default")
      (node (ref "J401") (pin "5") (pinfunction "5_5") (pintype "passive"))
      (node (ref "U101") (pin "8") (pinfunction "PC14_8") (pintype "bidirectional"))
    )
    (net (code "49") (name "GYRO_DRDY") (class "Default")
      (node (ref "U$501") (pin "9") (pinfunction "INT2_9") (pintype "bidirectional"))
      (node (ref "U101") (pin "35") (pinfunction "PB0_35") (pintype "bidirectional"))
    )
    (net (code "50") (name "IO-~{RESET}") (class "Default")
      (node (ref "U$702") (pin "3") (pinfunction "POR2_3") (pintype "bidirectional"))
    )
    (net (code "51") (name "MAG_DRDY") (class "Default")
      (node (ref "U$501") (pin "12") (pinfunction "DSYNC_12") (pintype "bidirectional"))
      (node (ref "U101") (pin "36") (pinfunction "PB1_36") (pintype "bidirectional"))
    )
    (net (code "52") (name "Net-(C101-1)") (class "Default")
      (node (ref "C101") (pin "P$1") (pinfunction "1_P$1") (pintype "passive"))
      (node (ref "U101") (pin "12") (pinfunction "OSC_IN_12") (pintype "input"))
      (node (ref "X101") (pin "3") (pinfunction "3_3") (pintype "bidirectional"))
    )
    (net (code "53") (name "Net-(C102-2)") (class "Default")
      (node (ref "C102") (pin "P$2") (pinfunction "2_P$2") (pintype "passive"))
      (node (ref "U101") (pin "13") (pinfunction "OSC_OUT_13") (pintype "output"))
      (node (ref "X101") (pin "1") (pinfunction "1_1") (pintype "bidirectional"))
    )
    (net (code "54") (name "Net-(C403-1)") (class "Default")
      (node (ref "C403") (pin "P$1") (pinfunction "1_P$1") (pintype "passive"))
      (node (ref "JP403") (pin "2") (pinfunction "2_2") (pintype "passive"))
      (node (ref "R405") (pin "P$2") (pinfunction "2_P$2") (pintype "passive"))
    )
    (net (code "55") (name "Net-(C404-1)") (class "Default")
      (node (ref "C404") (pin "P$1") (pinfunction "1_P$1") (pintype "passive"))
      (node (ref "JP403") (pin "1") (pinfunction "1_1") (pintype "passive"))
      (node (ref "R406") (pin "P$2") (pinfunction "2_P$2") (pintype "passive"))
    )
    (net (code "56") (name "Net-(C503-1)") (class "Default")
      (node (ref "C503") (pin "P$1") (pinfunction "1_P$1") (pintype "passive"))
      (node (ref "U$501") (pin "13") (pinfunction "REGD_13") (pintype "power_in"))
    )
    (net (code "57") (name "Net-(C603-1)") (class "Default")
      (node (ref "C603") (pin "P$1") (pinfunction "1_P$1") (pintype "passive"))
      (node (ref "U$601") (pin "10") (pinfunction "VAUX_10") (pintype "input"))
    )
    (net (code "58") (name "Net-(C703-2)") (class "Default")
      (node (ref "C703") (pin "P$2") (pinfunction "2_P$2") (pintype "passive"))
      (node (ref "U$701") (pin "6") (pinfunction "CSET_6") (pintype "bidirectional"))
    )
    (net (code "59") (name "Net-(C704-1)") (class "Default")
      (node (ref "C704") (pin "P$1") (pinfunction "1_P$1") (pintype "passive"))
      (node (ref "U$702") (pin "6") (pinfunction "CSET_6") (pintype "bidirectional"))
    )
    (net (code "60") (name "Net-(C715-1)") (class "Default")
      (node (ref "C715") (pin "P$1") (pinfunction "1_P$1") (pintype "passive"))
      (node (ref "U101") (pin "49") (pinfunction "VCAP_1_49") (pintype "power_in"))
    )
    (net (code "61") (name "Net-(C717-1)") (class "Default")
      (node (ref "C717") (pin "P$1") (pinfunction "1_P$1") (pintype "passive"))
      (node (ref "U101") (pin "73") (pinfunction "VCAP_2_73") (pintype "power_in"))
    )
    (net (code "62") (name "Net-(J401-Pad8)") (class "Default")
      (node (ref "J401") (pin "8") (pinfunction "8_8") (pintype "passive"))
      (node (ref "L401") (pin "P$2") (pinfunction "P$2_P$2") (pintype "bidirectional"))
    )
    (net (code "63") (name "Net-(J1001A-S)") (class "Default")
      (node (ref "J1001") (pin "S1") (pinfunction "S_S1") (pintype "passive"))
      (node (ref "L1001") (pin "P$9") (pinfunction "P$2_P$9") (pintype "bidirectional"))
    )
    (net (code "64") (name "Net-(J1001B-S)") (class "Default")
      (node (ref "J1001") (pin "S2") (pinfunction "S_S2") (pintype "passive"))
      (node (ref "L1001") (pin "P$10") (pinfunction "P$2_P$10") (pintype "bidirectional"))
    )
    (net (code "65") (name "Net-(J1001C-S)") (class "Default")
      (node (ref "J1001") (pin "S3") (pinfunction "S_S3") (pintype "passive"))
      (node (ref "L1001") (pin "P$12") (pinfunction "P$2_P$12") (pintype "bidirectional"))
    )
    (net (code "66") (name "Net-(J1001D-S)") (class "Default")
      (node (ref "J1001") (pin "S4") (pinfunction "S_S4") (pintype "passive"))
      (node (ref "L1001") (pin "P$11") (pinfunction "P$2_P$11") (pintype "bidirectional"))
    )
    (net (code "67") (name "Net-(J1001E-S)") (class "Default")
      (node (ref "J1001") (pin "S5") (pinfunction "S_S5") (pintype "passive"))
      (node (ref "L1001") (pin "P$13") (pinfunction "P$2_P$13") (pintype "bidirectional"))
    )
    (net (code "68") (name "Net-(J1001F-S)") (class "Default")
      (node (ref "J1001") (pin "S6") (pinfunction "S_S6") (pintype "passive"))
      (node (ref "L1001") (pin "P$14") (pinfunction "P$2_P$14") (pintype "bidirectional"))
    )
    (net (code "69") (name "Net-(J1001G-S)") (class "Default")
      (node (ref "J1001") (pin "S7") (pinfunction "S_S7") (pintype "passive"))
      (node (ref "L1001") (pin "P$15") (pinfunction "P$2_P$15") (pintype "bidirectional"))
    )
    (net (code "70") (name "Net-(J1001H-S)") (class "Default")
      (node (ref "J1001") (pin "S8") (pinfunction "S_S8") (pintype "passive"))
      (node (ref "L1001") (pin "P$16") (pinfunction "P$2_P$16") (pintype "bidirectional"))
    )
    (net (code "71") (name "Net-(JP201-Pad2)") (class "Default")
      (node (ref "JP201") (pin "2") (pinfunction "2_2") (pintype "passive"))
      (node (ref "JP202") (pin "2") (pinfunction "2_2") (pintype "bidirectional"))
      (node (ref "U$201") (pin "C") (pinfunction "C_C") (pintype "passive"))
    )
    (net (code "72") (name "Net-(JP203-Pad2)") (class "Default")
      (node (ref "JP203") (pin "2") (pinfunction "2_2") (pintype "bidirectional"))
      (node (ref "JP204") (pin "2") (pinfunction "2_2") (pintype "bidirectional"))
      (node (ref "JP205") (pin "2") (pinfunction "2_2") (pintype "bidirectional"))
      (node (ref "L203") (pin "P$2") (pinfunction "P$2_P$2") (pintype "bidirectional"))
      (node (ref "U$204") (pin "C") (pinfunction "C_C") (pintype "passive"))
    )
    (net (code "73") (name "Net-(JP401-Pad1)") (class "Default")
      (node (ref "JP401") (pin "1") (pinfunction "1_1") (pintype "passive"))
      (node (ref "JP402") (pin "1") (pinfunction "1_1") (pintype "passive"))
      (node (ref "L402") (pin "P$2") (pinfunction "P$2_P$2") (pintype "bidirectional"))
      (node (ref "U$401") (pin "C") (pinfunction "C_C") (pintype "passive"))
    )
    (net (code "74") (name "Net-(JP404-Pad1)") (class "Default")
      (node (ref "JP404") (pin "1") (pinfunction "1_1") (pintype "passive"))
      (node (ref "JP405") (pin "1") (pinfunction "1_1") (pintype "passive"))
      (node (ref "L404") (pin "P$2") (pinfunction "P$2_P$2") (pintype "bidirectional"))
      (node (ref "U$402") (pin "C") (pinfunction "C_C") (pintype "passive"))
    )
    (net (code "75") (name "Net-(JP1001-1)") (class "Default")
      (node (ref "JP1001") (pin "P$1") (pinfunction "1_P$1") (pintype "passive"))
      (node (ref "R1001") (pin "P$1") (pinfunction "1_P$1") (pintype "passive"))
    )
    (net (code "76") (name "Net-(JP1002-1)") (class "Default")
      (node (ref "JP1002") (pin "P$1") (pinfunction "1_P$1") (pintype "passive"))
      (node (ref "R1002") (pin "P$1") (pinfunction "1_P$1") (pintype "passive"))
    )
    (net (code "77") (name "Net-(L403B-P$2)") (class "Default")
      (node (ref "JP402") (pin "2") (pinfunction "2_2") (pintype "passive"))
      (node (ref "L403") (pin "P$15") (pinfunction "P$2_P$15") (pintype "bidirectional"))
    )
    (net (code "78") (name "Net-(L403D-P$2)") (class "Default")
      (node (ref "JP401") (pin "2") (pinfunction "2_2") (pintype "passive"))
      (node (ref "L403") (pin "P$13") (pinfunction "P$2_P$13") (pintype "bidirectional"))
    )
    (net (code "79") (name "Net-(L403G-P$2)") (class "Default")
      (node (ref "JP402") (pin "3") (pinfunction "3_3") (pintype "passive"))
      (node (ref "L403") (pin "P$10") (pinfunction "P$2_P$10") (pintype "bidirectional"))
    )
    (net (code "80") (name "Net-(L403H-P$2)") (class "Default")
      (node (ref "JP401") (pin "3") (pinfunction "3_3") (pintype "passive"))
      (node (ref "L403") (pin "P$9") (pinfunction "P$2_P$9") (pintype "bidirectional"))
    )
    (net (code "81") (name "Net-(R101-1)") (class "Default")
      (node (ref "R101") (pin "P$1") (pinfunction "1_P$1") (pintype "passive"))
      (node (ref "U101") (pin "37") (pinfunction "PB2_37") (pintype "bidirectional"))
    )
    (net (code "82") (name "Net-(R201-2)") (class "Default")
      (node (ref "JP202") (pin "1") (pinfunction "1_1") (pintype "bidirectional"))
      (node (ref "R201") (pin "P$2") (pinfunction "2_P$2") (pintype "passive"))
      (node (ref "R202") (pin "P$2") (pinfunction "2_P$2") (pintype "passive"))
      (node (ref "U$202") (pin "C") (pinfunction "C_C") (pintype "passive"))
    )
    (net (code "83") (name "Net-(R407-2)") (class "Default")
      (node (ref "R407") (pin "P$2") (pinfunction "2_P$2") (pintype "passive"))
      (node (ref "SJ402") (pin "1") (pinfunction "1_1") (pintype "passive"))
    )
    (net (code "84") (name "Net-(R408-1)") (class "Default")
      (node (ref "R408") (pin "P$1") (pinfunction "1_P$1") (pintype "passive"))
      (node (ref "SJ401") (pin "2") (pinfunction "2_2") (pintype "passive"))
    )
    (net (code "85") (name "Net-(R408-2)") (class "Default")
      (node (ref "JP404") (pin "3") (pinfunction "3_3") (pintype "passive"))
      (node (ref "R408") (pin "P$2") (pinfunction "2_P$2") (pintype "passive"))
      (node (ref "U401") (pin "6") (pinfunction "CANL_6") (pintype "bidirectional"))
    )
    (net (code "86") (name "Net-(R703-1)") (class "Default")
      (node (ref "R703") (pin "P$1") (pinfunction "1_P$1") (pintype "passive"))
      (node (ref "U$703") (pin "7") (pinfunction "ILIM_7") (pintype "bidirectional"))
    )
    (net (code "87") (name "Net-(R706-2)") (class "Default")
      (node (ref "D701") (pin "C") (pinfunction "C_C") (pintype "passive"))
      (node (ref "R706") (pin "P$2") (pinfunction "2_P$2") (pintype "passive"))
    )
    (net (code "88") (name "Net-(R801-1)") (class "Default")
      (node (ref "JP801") (pin "2") (pinfunction "2_2") (pintype "passive"))
      (node (ref "R801") (pin "P$1") (pinfunction "1_P$1") (pintype "passive"))
    )
    (net (code "89") (name "Net-(R803-1)") (class "Default")
      (node (ref "R803") (pin "P$1") (pinfunction "1_P$1") (pintype "passive"))
      (node (ref "R804") (pin "P$2") (pinfunction "2_P$2") (pintype "passive"))
    )
    (net (code "90") (name "Net-(R803-2)") (class "Default")
      (node (ref "LED801") (pin "C") (pinfunction "C_C") (pintype "passive"))
      (node (ref "R803") (pin "P$2") (pinfunction "2_P$2") (pintype "passive"))
    )
    (net (code "91") (name "Net-(R805-2)") (class "Default")
      (node (ref "LED802") (pin "C") (pinfunction "C_C") (pintype "passive"))
      (node (ref "R805") (pin "P$2") (pinfunction "2_P$2") (pintype "passive"))
    )
    (net (code "92") (name "Net-(R901-1)") (class "Default")
      (node (ref "D901") (pin "C") (pinfunction "C_C") (pintype "passive"))
      (node (ref "R901") (pin "P$1") (pinfunction "1_P$1") (pintype "passive"))
      (node (ref "R902") (pin "P$2") (pinfunction "2_P$2") (pintype "passive"))
    )
    (net (code "93") (name "Net-(U$301-D1I)") (class "Default")
      (node (ref "JP301") (pin "2") (pinfunction "2_2") (pintype "passive"))
      (node (ref "U$301") (pin "1") (pinfunction "D1I_1") (pintype "bidirectional"))
    )
    (net (code "94") (name "Net-(U$301-D2I)") (class "Default")
      (node (ref "JP301") (pin "3") (pinfunction "3_3") (pintype "passive"))
      (node (ref "U$301") (pin "3") (pinfunction "D2I_3") (pintype "bidirectional"))
    )
    (net (code "95") (name "Net-(U$601-L1)") (class "Default")
      (node (ref "L$601") (pin "2") (pinfunction "2_2") (pintype "passive"))
      (node (ref "U$601") (pin "1") (pinfunction "L1_1") (pintype "bidirectional"))
    )
    (net (code "96") (name "Net-(U$601-L2)") (class "Default")
      (node (ref "L$601") (pin "1") (pinfunction "1_1") (pintype "passive"))
      (node (ref "U$601") (pin "14") (pinfunction "L2_14") (pintype "bidirectional"))
    )
    (net (code "97") (name "Net-(U401-CANH)") (class "Default")
      (node (ref "JP404") (pin "2") (pinfunction "2_2") (pintype "passive"))
      (node (ref "SJ401") (pin "1") (pinfunction "1_1") (pintype "passive"))
      (node (ref "U401") (pin "7") (pinfunction "CANH_7") (pintype "bidirectional"))
    )
    (net (code "98") (name "OTG_FS_DM") (class "Default")
      (node (ref "U$301") (pin "6") (pinfunction "D1O_6") (pintype "bidirectional"))
      (node (ref "U101") (pin "70") (pinfunction "PA11_70") (pintype "bidirectional"))
    )
    (net (code "99") (name "OTG_FS_DP") (class "Default")
      (node (ref "U$301") (pin "4") (pinfunction "D2O_4") (pintype "bidirectional"))
      (node (ref "U101") (pin "71") (pinfunction "PA12_71") (pintype "bidirectional"))
    )
    (net (code "100") (name "PPM_INPUT") (class "Default")
      (node (ref "R201") (pin "P$1") (pinfunction "1_P$1") (pintype "passive"))
      (node (ref "R203") (pin "P$1") (pinfunction "1_P$1") (pintype "passive"))
      (node (ref "U$203") (pin "2") (pinfunction "1A_2") (pintype "bidirectional"))
      (node (ref "U101") (pin "23") (pinfunction "PA0_23") (pintype "bidirectional"))
    )
    (net (code "101") (name "SAFETY") (class "Default")
      (node (ref "JP801") (pin "3") (pinfunction "3_3") (pintype "passive"))
      (node (ref "R802") (pin "P$1") (pinfunction "1_P$1") (pintype "passive"))
      (node (ref "U101") (pin "93") (pinfunction "PB7_93") (pintype "bidirectional"))
    )
    (net (code "102") (name "SBUS_OUTPUT_ENABLE") (class "Default")
      (node (ref "R204") (pin "P$2") (pinfunction "2_P$2") (pintype "passive"))
      (node (ref "U$203") (pin "7") (pinfunction "~{2OE}_7") (pintype "input"))
      (node (ref "U101") (pin "91") (pinfunction "PB5_91") (pintype "bidirectional"))
    )
    (net (code "103") (name "SDIO_CK") (class "Default")
      (node (ref "U$302") (pin "6") (pinfunction "CLK_6") (pintype "bidirectional"))
      (node (ref "U101") (pin "80") (pinfunction "PC12_80") (pintype "bidirectional"))
    )
    (net (code "104") (name "SDIO_CMD") (class "Default")
      (node (ref "U$302") (pin "1") (pinfunction "~{CS}_1") (pintype "bidirectional"))
      (node (ref "U101") (pin "83") (pinfunction "PD2_83") (pintype "bidirectional"))
    )
    (net (code "105") (name "SDIO_D0") (class "Default")
      (node (ref "U$302") (pin "5") (pinfunction "DI/IO0_5") (pintype "bidirectional"))
      (node (ref "U101") (pin "65") (pinfunction "PC8_65") (pintype "bidirectional"))
    )
    (net (code "106") (name "SDIO_D1") (class "Default")
      (node (ref "U$302") (pin "2") (pinfunction "DO/IO1_2") (pintype "bidirectional"))
      (node (ref "U101") (pin "66") (pinfunction "PC9_66") (pintype "bidirectional"))
    )
    (net (code "107") (name "SDIO_D2") (class "Default")
      (node (ref "U$302") (pin "3") (pinfunction "~{WP}/IO2_3") (pintype "bidirectional"))
      (node (ref "U101") (pin "78") (pinfunction "PC10_78") (pintype "bidirectional"))
    )
    (net (code "108") (name "SDIO_D3") (class "Default")
      (node (ref "U$302") (pin "7") (pinfunction "~{HOLD}/IO3_7") (pintype "bidirectional"))
      (node (ref "U101") (pin "79") (pinfunction "PC11_79") (pintype "bidirectional"))
    )
    (net (code "109") (name "SERIAL1_CTS") (class "Default")
      (node (ref "JP203") (pin "6") (pinfunction "6_6") (pintype "bidirectional"))
      (node (ref "L201") (pin "P$16") (pinfunction "P$2_P$16") (pintype "bidirectional"))
    )
    (net (code "110") (name "SERIAL1_RTS") (class "Default")
      (node (ref "JP203") (pin "4") (pinfunction "4_4") (pintype "bidirectional"))
      (node (ref "L201") (pin "P$15") (pinfunction "P$2_P$15") (pintype "bidirectional"))
    )
    (net (code "111") (name "SERIAL1_RX") (class "Default")
      (node (ref "JP203") (pin "3") (pinfunction "3_3") (pintype "bidirectional"))
      (node (ref "L201") (pin "P$13") (pinfunction "P$2_P$13") (pintype "bidirectional"))
    )
    (net (code "112") (name "SERIAL1_TX") (class "Default")
      (node (ref "JP203") (pin "1") (pinfunction "1_1") (pintype "bidirectional"))
      (node (ref "L201") (pin "P$14") (pinfunction "P$2_P$14") (pintype "bidirectional"))
    )
    (net (code "113") (name "SERIAL2_CTS") (class "Default")
      (node (ref "JP204") (pin "6") (pinfunction "6_6") (pintype "bidirectional"))
      (node (ref "L201") (pin "P$10") (pinfunction "P$2_P$10") (pintype "bidirectional"))
    )
    (net (code "114") (name "SERIAL2_RTS") (class "Default")
      (node (ref "JP204") (pin "4") (pinfunction "4_4") (pintype "bidirectional"))
      (node (ref "L201") (pin "P$9") (pinfunction "P$2_P$9") (pintype "bidirectional"))
    )
    (net (code "115") (name "SERIAL2_RX") (class "Default")
      (node (ref "JP204") (pin "3") (pinfunction "3_3") (pintype "bidirectional"))
      (node (ref "L201") (pin "P$11") (pinfunction "P$2_P$11") (pintype "bidirectional"))
    )
    (net (code "116") (name "SERIAL2_TX") (class "Default")
      (node (ref "JP204") (pin "1") (pinfunction "1_1") (pintype "bidirectional"))
      (node (ref "L201") (pin "P$12") (pinfunction "P$2_P$12") (pintype "bidirectional"))
    )
    (net (code "117") (name "SERIAL3_RX") (class "Default")
      (node (ref "JP205") (pin "3") (pinfunction "3_3") (pintype "bidirectional"))
      (node (ref "L202") (pin "P$9") (pinfunction "P$2_P$9") (pintype "bidirectional"))
    )
    (net (code "118") (name "SERIAL3_TX") (class "Default")
      (node (ref "JP205") (pin "1") (pinfunction "1_1") (pintype "bidirectional"))
      (node (ref "L202") (pin "P$11") (pinfunction "P$2_P$11") (pintype "bidirectional"))
    )
    (net (code "119") (name "SPEKTRUM_RX") (class "Default")
      (node (ref "R202") (pin "P$1") (pinfunction "1_P$1") (pintype "passive"))
      (node (ref "U101") (pin "69") (pinfunction "PA10_69") (pintype "bidirectional"))
    )
    (net (code "120") (name "SPI_EXT_MISO") (class "Default")
      (node (ref "J401") (pin "3") (pinfunction "3_3") (pintype "passive"))
      (node (ref "U101") (pin "4") (pinfunction "PE5_4") (pintype "bidirectional"))
    )
    (net (code "121") (name "SPI_EXT_MOSI") (class "Default")
      (node (ref "J401") (pin "6") (pinfunction "6_6") (pintype "passive"))
      (node (ref "U101") (pin "5") (pinfunction "PE6_5") (pintype "bidirectional"))
    )
    (net (code "122") (name "SPI_EXT_SCK") (class "Default")
      (node (ref "J401") (pin "2") (pinfunction "2_2") (pintype "passive"))
      (node (ref "U101") (pin "1") (pinfunction "PE2_1") (pintype "bidirectional"))
    )
    (net (code "123") (name "SPI_INT_MISO") (class "Default")
      (node (ref "U$501") (pin "7") (pinfunction "SA0/MISO_7") (pintype "bidirectional"))
      (node (ref "U101") (pin "31") (pinfunction "PA6_31") (pintype "bidirectional"))
    )
    (net (code "124") (name "SPI_INT_MOSI") (class "Default")
      (node (ref "U$501") (pin "6") (pinfunction "SDA/MOSI_6") (pintype "bidirectional"))
      (node (ref "U101") (pin "32") (pinfunction "PA7_32") (pintype "bidirectional"))
    )
    (net (code "125") (name "SPI_INT_SCK") (class "Default")
      (node (ref "U$501") (pin "4") (pinfunction "SCL/CLK_4") (pintype "bidirectional"))
      (node (ref "U101") (pin "30") (pinfunction "PA5_30") (pintype "bidirectional"))
    )
    (net (code "126") (name "VBAT") (class "Default")
      (node (ref "R706") (pin "P$1") (pinfunction "1_P$1") (pintype "passive"))
      (node (ref "U$704") (pin "1") (pinfunction "POS_1") (pintype "bidirectional"))
      (node (ref "U101") (pin "6") (pinfunction "VBAT_6") (pintype "power_in"))
    )
    (net (code "127") (name "VBUS") (class "Default")
      (node (ref "D904") (pin "ANODE") (pinfunction "A_ANODE") (pintype "passive"))
      (node (ref "JP301") (pin "1") (pinfunction "1_1") (pintype "passive"))
      (node (ref "U$301") (pin "5") (pinfunction "VBUS_5") (pintype "bidirectional"))
      (node (ref "U101") (pin "68") (pinfunction "PA9_68") (pintype "bidirectional"))
    )
    (net (code "128") (name "VDD_3V3_SENSORS") (class "Default")
      (node (ref "C501") (pin "P$1") (pinfunction "1_P$1") (pintype "passive"))
      (node (ref "C502") (pin "P$1") (pinfunction "1_P$1") (pintype "passive"))
      (node (ref "C707") (pin "P$1") (pinfunction "1_P$1") (pintype "passive"))
      (node (ref "U$501") (pin "1") (pinfunction "VDD_IO_1") (pintype "power_in"))
      (node (ref "U$501") (pin "14") (pinfunction "VDD_14") (pintype "power_in"))
      (node (ref "U$501") (pin "15") (pinfunction "RSV2_15") (pintype "input"))
      (node (ref "U$702") (pin "8") (pinfunction "VOUT1_8") (pintype "bidirectional"))
    )
    (net (code "129") (name "VDD_3V3_SENSORS_EN") (class "Default")
      (node (ref "R702") (pin "P$2") (pinfunction "2_P$2") (pintype "passive"))
      (node (ref "U$702") (pin "5") (pinfunction "EN1_5") (pintype "bidirectional"))
      (node (ref "U101") (pin "2") (pinfunction "PE3_2") (pintype "bidirectional"))
    )
    (net (code "130") (name "VDD_3V3_SPEKTRUM") (class "Default")
      (node (ref "C708") (pin "P$1") (pinfunction "1_P$1") (pintype "passive"))
      (node (ref "JP201") (pin "1") (pinfunction "1_1") (pintype "passive"))
      (node (ref "U$701") (pin "8") (pinfunction "VOUT1_8") (pintype "bidirectional"))
    )
    (net (code "131") (name "VDD_3V3_SPEKTRUM_EN") (class "Default")
      (node (ref "R701") (pin "P$2") (pinfunction "2_P$2") (pintype "passive"))
      (node (ref "U$701") (pin "5") (pinfunction "EN1_5") (pintype "bidirectional"))
      (node (ref "U101") (pin "17") (pinfunction "PC2_17") (pintype "bidirectional"))
    )
    (net (code "132") (name "VDD_5V") (class "Default")
      (node (ref "C604") (pin "1") (pinfunction "1_1") (pintype "passive"))
      (node (ref "C605") (pin "1") (pinfunction "1_1") (pintype "passive"))
      (node (ref "C606") (pin "1") (pinfunction "1_1") (pintype "passive"))
      (node (ref "C701") (pin "P$1") (pinfunction "1_P$1") (pintype "passive"))
      (node (ref "C702") (pin "P$1") (pinfunction "1_P$1") (pintype "passive"))
      (node (ref "LED801") (pin "A") (pinfunction "A_A") (pintype "passive"))
      (node (ref "LED802") (pin "A") (pinfunction "A_A") (pintype "passive"))
      (node (ref "R707") (pin "P$2") (pinfunction "2_P$2") (pintype "passive"))
      (node (ref "U$601") (pin "13") (pinfunction "VOUT_13") (pintype "power_in"))
      (node (ref "U$701") (pin "1") (pinfunction "VIN_1") (pintype "bidirectional"))
      (node (ref "U$701") (pin "4") (pinfunction "EN2_4") (pintype "bidirectional"))
      (node (ref "U$702") (pin "1") (pinfunction "VIN_1") (pintype "bidirectional"))
      (node (ref "U$703") (pin "1") (pinfunction "IN_1") (pintype "bidirectional"))
    )
    (net (code "133") (name "VDD_5V_PERIPH") (class "Default")
      (node (ref "JP201") (pin "3") (pinfunction "3_3") (pintype "passive"))
      (node (ref "L203") (pin "P$1") (pinfunction "P$1_P$1") (pintype "bidirectional"))
      (node (ref "L401") (pin "P$1") (pinfunction "P$1_P$1") (pintype "bidirectional"))
      (node (ref "L402") (pin "P$1") (pinfunction "P$1_P$1") (pintype "bidirectional"))
      (node (ref "L404") (pin "P$1") (pinfunction "P$1_P$1") (pintype "bidirectional"))
      (node (ref "U$703") (pin "8") (pinfunction "OUT_8") (pintype "bidirectional"))
    )
    (net (code "134") (name "VDD_5V_SENS") (class "Default")
      (node (ref "R707") (pin "P$1") (pinfunction "1_P$1") (pintype "passive"))
      (node (ref "R708") (pin "P$1") (pinfunction "1_P$1") (pintype "passive"))
      (node (ref "U101") (pin "29") (pinfunction "PA4_29") (pintype "bidirectional"))
    )
    (net (code "135") (name "VDD_IN") (class "Default")
      (node (ref "C601") (pin "1") (pinfunction "1_1") (pintype "passive"))
      (node (ref "C602") (pin "P$1") (pinfunction "1_P$1") (pintype "passive"))
      (node (ref "D902") (pin "C") (pinfunction "C_C") (pintype "passive"))
      (node (ref "D903") (pin "C") (pinfunction "C_C") (pintype "passive"))
      (node (ref "D904") (pin "CATHODE") (pinfunction "C_CATHODE") (pintype "passive"))
      (node (ref "U$601") (pin "2") (pinfunction "VIN_2") (pintype "power_in"))
      (node (ref "U$601") (pin "3") (pinfunction "EN_3") (pintype "input"))
    )
    (net (code "136") (name "VDD_SERVO_SENSE") (class "Default")
      (node (ref "R902") (pin "P$1") (pinfunction "1_P$1") (pintype "passive"))
      (node (ref "R903") (pin "P$2") (pinfunction "2_P$2") (pintype "passive"))
      (node (ref "U101") (pin "16") (pinfunction "PC1_16") (pintype "bidirectional"))
    )
    (net (code "137") (name "V_EXT") (class "Default")
      (node (ref "D903") (pin "A") (pinfunction "A_A") (pintype "passive"))
      (node (ref "JP901") (pin "1") (pinfunction "1_1") (pintype "passive"))
      (node (ref "R901") (pin "P$2") (pinfunction "2_P$2") (pintype "passive"))
    )
    (net (code "138") (name "V_SERVO") (class "Default")
      (node (ref "D902") (pin "A") (pinfunction "A_A") (pintype "passive"))
      (node (ref "J1001") (pin "PWR_S1") (pinfunction "S_PWR_S1") (pintype "passive"))
      (node (ref "J1001") (pin "PWR_S2") (pinfunction "S_PWR_S2") (pintype "passive"))
      (node (ref "J1001") (pin "PWR_S3") (pinfunction "S_PWR_S3") (pintype "passive"))
      (node (ref "J1001") (pin "PWR_S4") (pinfunction "S_PWR_S4") (pintype "passive"))
      (node (ref "J1001") (pin "PWR_S5") (pinfunction "S_PWR_S5") (pintype "passive"))
      (node (ref "J1001") (pin "PWR_S6") (pinfunction "S_PWR_S6") (pintype "passive"))
      (node (ref "J1001") (pin "PWR_S7") (pinfunction "S_PWR_S7") (pintype "passive"))
      (node (ref "J1001") (pin "PWR_S8") (pinfunction "S_PWR_S8") (pintype "passive"))
    )
    (net (code "139") (name "unconnected-(J401-Pad1)") (class "Default")
      (node (ref "J401") (pin "1") (pinfunction "1_1") (pintype "passive"))
    )
    (net (code "140") (name "unconnected-(JP205-Pad4)") (class "Default")
      (node (ref "JP205") (pin "4") (pinfunction "4_4") (pintype "bidirectional"))
    )
    (net (code "141") (name "unconnected-(JP205-Pad6)") (class "Default")
      (node (ref "JP205") (pin "6") (pinfunction "6_6") (pintype "bidirectional"))
    )
    (net (code "142") (name "unconnected-(JX301F-S-Pad8)") (class "Default")
      (node (ref "JX301") (pin "8") (pinfunction "S_8") (pintype "passive"))
    )
    (net (code "143") (name "unconnected-(L202-PadP$1)") (class "Default")
      (node (ref "L202") (pin "P$1") (pinfunction "P$1_P$1") (pintype "bidirectional"))
    )
    (net (code "144") (name "unconnected-(L202A-P$2-PadP$16)") (class "Default")
      (node (ref "L202") (pin "P$16") (pinfunction "P$2_P$16") (pintype "bidirectional"))
    )
    (net (code "145") (name "unconnected-(L202B-P$1-PadP$2)") (class "Default")
      (node (ref "L202") (pin "P$2") (pinfunction "P$1_P$2") (pintype "bidirectional"))
    )
    (net (code "146") (name "unconnected-(L202B-P$2-PadP$15)") (class "Default")
      (node (ref "L202") (pin "P$15") (pinfunction "P$2_P$15") (pintype "bidirectional"))
    )
    (net (code "147") (name "unconnected-(L202C-P$1-PadP$3)") (class "Default")
      (node (ref "L202") (pin "P$3") (pinfunction "P$1_P$3") (pintype "bidirectional"))
    )
    (net (code "148") (name "unconnected-(L202C-P$2-PadP$14)") (class "Default")
      (node (ref "L202") (pin "P$14") (pinfunction "P$2_P$14") (pintype "bidirectional"))
    )
    (net (code "149") (name "unconnected-(L202D-P$1-PadP$4)") (class "Default")
      (node (ref "L202") (pin "P$4") (pinfunction "P$1_P$4") (pintype "bidirectional"))
    )
    (net (code "150") (name "unconnected-(L202D-P$2-PadP$13)") (class "Default")
      (node (ref "L202") (pin "P$13") (pinfunction "P$2_P$13") (pintype "bidirectional"))
    )
    (net (code "151") (name "unconnected-(L202E-P$1-PadP$5)") (class "Default")
      (node (ref "L202") (pin "P$5") (pinfunction "P$1_P$5") (pintype "bidirectional"))
    )
    (net (code "152") (name "unconnected-(L202E-P$2-PadP$12)") (class "Default")
      (node (ref "L202") (pin "P$12") (pinfunction "P$2_P$12") (pintype "bidirectional"))
    )
    (net (code "153") (name "unconnected-(L202G-P$1-PadP$7)") (class "Default")
      (node (ref "L202") (pin "P$7") (pinfunction "P$1_P$7") (pintype "bidirectional"))
    )
    (net (code "154") (name "unconnected-(L202G-P$2-PadP$10)") (class "Default")
      (node (ref "L202") (pin "P$10") (pinfunction "P$2_P$10") (pintype "bidirectional"))
    )
    (net (code "155") (name "unconnected-(L403-PadP$1)") (class "Default")
      (node (ref "L403") (pin "P$1") (pinfunction "P$1_P$1") (pintype "bidirectional"))
    )
    (net (code "156") (name "unconnected-(L403A-P$2-PadP$16)") (class "Default")
      (node (ref "L403") (pin "P$16") (pinfunction "P$2_P$16") (pintype "bidirectional"))
    )
    (net (code "157") (name "unconnected-(L403C-P$1-PadP$3)") (class "Default")
      (node (ref "L403") (pin "P$3") (pinfunction "P$1_P$3") (pintype "bidirectional"))
    )
    (net (code "158") (name "unconnected-(L403C-P$2-PadP$14)") (class "Default")
      (node (ref "L403") (pin "P$14") (pinfunction "P$2_P$14") (pintype "bidirectional"))
    )
    (net (code "159") (name "unconnected-(L403E-P$1-PadP$5)") (class "Default")
      (node (ref "L403") (pin "P$5") (pinfunction "P$1_P$5") (pintype "bidirectional"))
    )
    (net (code "160") (name "unconnected-(L403E-P$2-PadP$12)") (class "Default")
      (node (ref "L403") (pin "P$12") (pinfunction "P$2_P$12") (pintype "bidirectional"))
    )
    (net (code "161") (name "unconnected-(L403F-P$1-PadP$6)") (class "Default")
      (node (ref "L403") (pin "P$6") (pinfunction "P$1_P$6") (pintype "bidirectional"))
    )
    (net (code "162") (name "unconnected-(L403F-P$2-PadP$11)") (class "Default")
      (node (ref "L403") (pin "P$11") (pinfunction "P$2_P$11") (pintype "bidirectional"))
    )
    (net (code "163") (name "unconnected-(U$501-MST_SCL-Pad2)") (class "Default")
      (node (ref "U$501") (pin "2") (pinfunction "MST_SCL_2") (pintype "bidirectional"))
    )
    (net (code "164") (name "unconnected-(U$501-MST_SDA-Pad3)") (class "Default")
      (node (ref "U$501") (pin "3") (pinfunction "MST_SDA_3") (pintype "bidirectional"))
    )
    (net (code "165") (name "unconnected-(U$501-RSV3-Pad16)") (class "Default")
      (node (ref "U$501") (pin "16") (pinfunction "RSV3_16") (pintype "no_connect"))
    )
    (net (code "166") (name "unconnected-(U$601-FB-Pad12)") (class "Default")
      (node (ref "U$601") (pin "12") (pinfunction "FB_12") (pintype "input"))
    )
    (net (code "167") (name "unconnected-(U$601-PG-Pad5)") (class "Default")
      (node (ref "U$601") (pin "5") (pinfunction "PG_5") (pintype "output"))
    )
    (net (code "168") (name "unconnected-(U$702-VOUT2-Pad7)") (class "Default")
      (node (ref "U$702") (pin "7") (pinfunction "VOUT2_7") (pintype "bidirectional"))
    )
    (net (code "169") (name "unconnected-(U101I-PC0-Pad15)") (class "Default")
      (node (ref "U101") (pin "15") (pinfunction "PC0_15") (pintype "bidirectional"))
    )
    (net (code "170") (name "unconnected-(U101I-PC5-Pad34)") (class "Default")
      (node (ref "U101") (pin "34") (pinfunction "PC5_34") (pintype "bidirectional"))
    )
    (net (code "171") (name "unconnected-(U101I-PC6-Pad63)") (class "Default")
      (node (ref "U101") (pin "63") (pinfunction "PC6_63") (pintype "bidirectional"))
    )
    (net (code "172") (name "unconnected-(U101I-PC7-Pad64)") (class "Default")
      (node (ref "U101") (pin "64") (pinfunction "PC7_64") (pintype "bidirectional"))
    )
    (net (code "173") (name "unconnected-(U101L-PE10-Pad41)") (class "Default")
      (node (ref "U101") (pin "41") (pinfunction "PE10_41") (pintype "bidirectional"))
    )
    (net (code "174") (name "~{BARO_CS}") (class "Default")
      (node (ref "U101") (pin "88") (pinfunction "PD7_88") (pintype "bidirectional"))
    )
    (net (code "175") (name "~{FMU-LED_AMBER}") (class "Default")
      (node (ref "R804") (pin "P$1") (pinfunction "1_P$1") (pintype "passive"))
      (node (ref "U101") (pin "43") (pinfunction "PE12_43") (pintype "bidirectional"))
    )
    (net (code "176") (name "~{FRAM_CS}") (class "Default")
      (node (ref "U101") (pin "57") (pinfunction "PD10_57") (pintype "bidirectional"))
    )
    (net (code "177") (name "~{GYRO_CS}") (class "Default")
      (node (ref "U$501") (pin "8") (pinfunction "CS_8") (pintype "bidirectional"))
      (node (ref "U101") (pin "7") (pinfunction "PC13_7") (pintype "bidirectional"))
    )
    (net (code "178") (name "~{SPI_EXT_NSS}") (class "Default")
      (node (ref "J401") (pin "4") (pinfunction "4_4") (pintype "passive"))
      (node (ref "U101") (pin "3") (pinfunction "PE4_3") (pintype "bidirectional"))
    )
    (net (code "179") (name "~{VDD_5V_PERIPH_EN}") (class "Default")
      (node (ref "R704") (pin "P$2") (pinfunction "2_P$2") (pintype "passive"))
      (node (ref "U$703") (pin "5") (pinfunction "~{CE}_5") (pintype "bidirectional"))
      (node (ref "U101") (pin "67") (pinfunction "PA8_67") (pintype "bidirectional"))
    )
    (net (code "180") (name "~{VDD_5V_PERIPH_OC}") (class "Default")
      (node (ref "R705") (pin "P$2") (pinfunction "2_P$2") (pintype "passive"))
      (node (ref "U$703") (pin "4") (pinfunction "~{FAULT}_4") (pintype "bidirectional"))
      (node (ref "U101") (pin "46") (pinfunction "PE15_46") (pintype "bidirectional"))
    )
  )
)
